# PCB_3U_BNC.net
KiCad netlist of a schematic drawn in Altium Designer
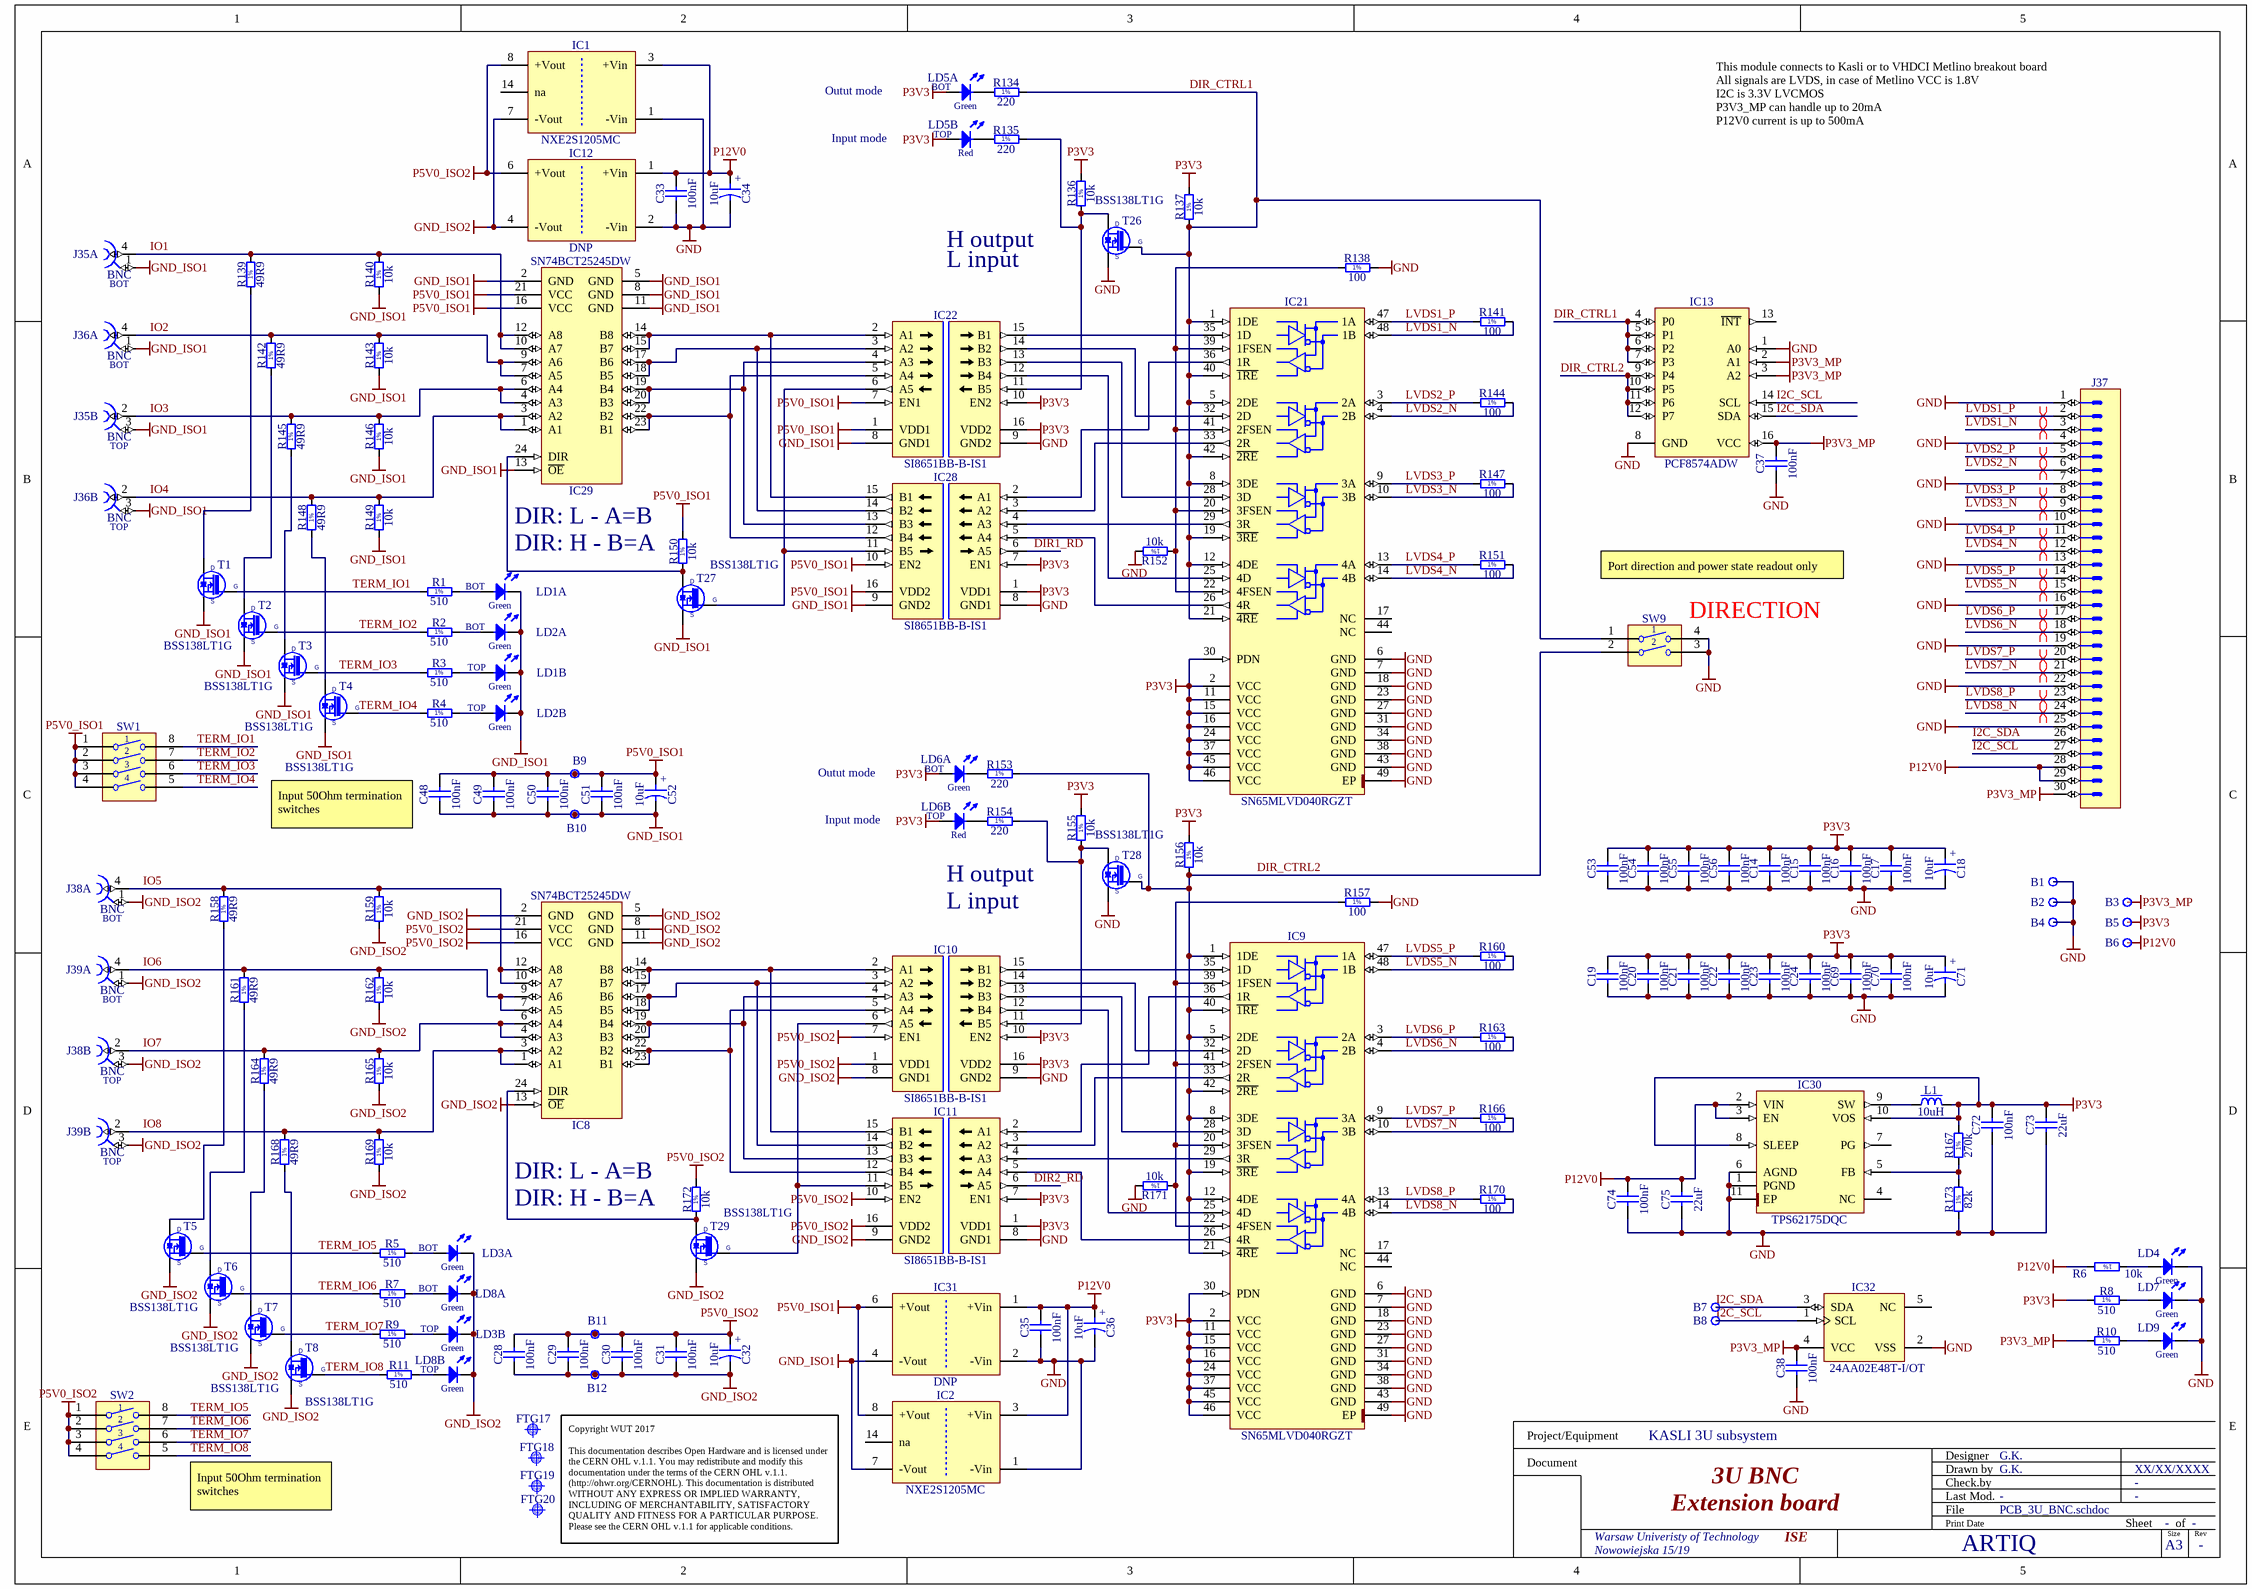
[diagram p0: PCB_3U_BNC.schdoc]

(export (version "E")
  (design (tool "Eeschema 10.0.6"))
  (components
    (comp (ref "B1")
      (value "Plated Hole")
      (footprint "c130h60")
      (description "Single Terminal Socket")
      (fields (field (name "PART NUMBER") "PLATED_HOLE0.6_PAD1.3") (field (name "AUTHOR") "CERN DEM MR"))
      (libsource (lib "Eletro-mechanical") (part "Single Terminal Socket"))
    )
    (comp (ref "B2")
      (value "Plated Hole")
      (footprint "c130h60")
      (description "Single Terminal Socket")
      (fields (field (name "PART NUMBER") "PLATED_HOLE0.6_PAD1.3") (field (name "AUTHOR") "CERN DEM MR"))
      (libsource (lib "Eletro-mechanical") (part "Single Terminal Socket"))
    )
    (comp (ref "B3")
      (value "Plated Hole")
      (footprint "c130h60")
      (description "Single Terminal Socket")
      (fields (field (name "PART NUMBER") "PLATED_HOLE0.6_PAD1.3") (field (name "AUTHOR") "CERN DEM MR"))
      (libsource (lib "Eletro-mechanical") (part "Single Terminal Socket"))
    )
    (comp (ref "B4")
      (value "Plated Hole")
      (footprint "c130h60")
      (description "Single Terminal Socket")
      (fields (field (name "PART NUMBER") "PLATED_HOLE0.6_PAD1.3") (field (name "AUTHOR") "CERN DEM MR"))
      (libsource (lib "Eletro-mechanical") (part "Single Terminal Socket"))
    )
    (comp (ref "B5")
      (value "Plated Hole")
      (footprint "c130h60")
      (description "Single Terminal Socket")
      (fields (field (name "PART NUMBER") "PLATED_HOLE0.6_PAD1.3") (field (name "AUTHOR") "CERN DEM MR"))
      (libsource (lib "Eletro-mechanical") (part "Single Terminal Socket"))
    )
    (comp (ref "B6")
      (value "Plated Hole")
      (footprint "c130h60")
      (description "Single Terminal Socket")
      (fields (field (name "PART NUMBER") "PLATED_HOLE0.6_PAD1.3") (field (name "AUTHOR") "CERN DEM MR"))
      (libsource (lib "Eletro-mechanical") (part "Single Terminal Socket"))
    )
    (comp (ref "B7")
      (value "Plated Hole")
      (footprint "c130h60")
      (description "Single Terminal Socket")
      (fields (field (name "PART NUMBER") "PLATED_HOLE0.6_PAD1.3") (field (name "AUTHOR") "CERN DEM MR"))
      (libsource (lib "Eletro-mechanical") (part "Single Terminal Socket"))
    )
    (comp (ref "B8")
      (value "Plated Hole")
      (footprint "c130h60")
      (description "Single Terminal Socket")
      (fields (field (name "PART NUMBER") "PLATED_HOLE0.6_PAD1.3") (field (name "AUTHOR") "CERN DEM MR"))
      (libsource (lib "Eletro-mechanical") (part "Single Terminal Socket"))
    )
    (comp (ref "B9")
      (value "Plated Hole")
      (footprint "c130h60")
      (description "Single Terminal Socket")
      (fields (field (name "PART NUMBER") "PLATED_HOLE0.6_PAD1.3") (field (name "AUTHOR") "CERN DEM MR"))
      (libsource (lib "Eletro-mechanical") (part "Single Terminal Socket"))
    )
    (comp (ref "B10")
      (value "Plated Hole")
      (footprint "c130h60")
      (description "Single Terminal Socket")
      (fields (field (name "PART NUMBER") "PLATED_HOLE0.6_PAD1.3") (field (name "AUTHOR") "CERN DEM MR"))
      (libsource (lib "Eletro-mechanical") (part "Single Terminal Socket"))
    )
    (comp (ref "B11")
      (value "Plated Hole")
      (footprint "c130h60")
      (description "Single Terminal Socket")
      (fields (field (name "PART NUMBER") "PLATED_HOLE0.6_PAD1.3") (field (name "AUTHOR") "CERN DEM MR"))
      (libsource (lib "Eletro-mechanical") (part "Single Terminal Socket"))
    )
    (comp (ref "B12")
      (value "Plated Hole")
      (footprint "c130h60")
      (description "Single Terminal Socket")
      (fields (field (name "PART NUMBER") "PLATED_HOLE0.6_PAD1.3") (field (name "AUTHOR") "CERN DEM MR"))
      (libsource (lib "Eletro-mechanical") (part "Single Terminal Socket"))
    )
    (comp (ref "C14")
      (value "100nF")
      (footprint "CAPC1005X55N")
      (description "Non-polarised capacitor")
      (fields
        (field (name "PART NUMBER") "CC0402_100NF_16V_10%_X5R")
        (field (name "VOLTAGE") "16V")
        (field (name "AUTHOR") "CERN DEM JLC")
      )
      (libsource (lib "Capacitors") (part "Capacitor - non polarized"))
    )
    (comp (ref "C15")
      (value "100nF")
      (footprint "CAPC1005X55N")
      (description "Non-polarised capacitor")
      (fields
        (field (name "PART NUMBER") "CC0402_100NF_16V_10%_X5R")
        (field (name "VOLTAGE") "16V")
        (field (name "AUTHOR") "CERN DEM JLC")
      )
      (libsource (lib "Capacitors") (part "Capacitor - non polarized"))
    )
    (comp (ref "C16")
      (value "100nF")
      (footprint "CAPC1005X55N")
      (description "Non-polarised capacitor")
      (fields
        (field (name "PART NUMBER") "CC0402_100NF_16V_10%_X5R")
        (field (name "VOLTAGE") "16V")
        (field (name "AUTHOR") "CERN DEM JLC")
      )
      (libsource (lib "Capacitors") (part "Capacitor - non polarized"))
    )
    (comp (ref "C17")
      (value "100nF")
      (footprint "CAPC1005X55N")
      (description "Non-polarised capacitor")
      (fields
        (field (name "PART NUMBER") "CC0402_100NF_16V_10%_X5R")
        (field (name "VOLTAGE") "16V")
        (field (name "AUTHOR") "CERN DEM JLC")
      )
      (libsource (lib "Capacitors") (part "Capacitor - non polarized"))
    )
    (comp (ref "C18")
      (value "10uF")
      (footprint "CAPAE430X540N")
      (description "Polarised capacitor")
      (fields
        (field (name "PART NUMBER") "CAE430-540_10UF_16V_20%")
        (field (name "VOLTAGE") "16V")
        (field (name "AUTHOR") "CERN DEM JLC")
      )
      (libsource (lib "Capacitors") (part "Capacitor - polarized"))
    )
    (comp (ref "C19")
      (value "100nF")
      (footprint "CAPC1005X55N")
      (description "Non-polarised capacitor")
      (fields
        (field (name "PART NUMBER") "CC0402_100NF_16V_10%_X5R")
        (field (name "VOLTAGE") "16V")
        (field (name "AUTHOR") "CERN DEM JLC")
      )
      (libsource (lib "Capacitors") (part "Capacitor - non polarized"))
    )
    (comp (ref "C20")
      (value "100nF")
      (footprint "CAPC1005X55N")
      (description "Non-polarised capacitor")
      (fields
        (field (name "PART NUMBER") "CC0402_100NF_16V_10%_X5R")
        (field (name "VOLTAGE") "16V")
        (field (name "AUTHOR") "CERN DEM JLC")
      )
      (libsource (lib "Capacitors") (part "Capacitor - non polarized"))
    )
    (comp (ref "C21")
      (value "100nF")
      (footprint "CAPC1005X55N")
      (description "Non-polarised capacitor")
      (fields
        (field (name "PART NUMBER") "CC0402_100NF_16V_10%_X5R")
        (field (name "VOLTAGE") "16V")
        (field (name "AUTHOR") "CERN DEM JLC")
      )
      (libsource (lib "Capacitors") (part "Capacitor - non polarized"))
    )
    (comp (ref "C22")
      (value "100nF")
      (footprint "CAPC1005X55N")
      (description "Non-polarised capacitor")
      (fields
        (field (name "PART NUMBER") "CC0402_100NF_16V_10%_X5R")
        (field (name "VOLTAGE") "16V")
        (field (name "AUTHOR") "CERN DEM JLC")
      )
      (libsource (lib "Capacitors") (part "Capacitor - non polarized"))
    )
    (comp (ref "C23")
      (value "100nF")
      (footprint "CAPC1005X55N")
      (description "Non-polarised capacitor")
      (fields
        (field (name "PART NUMBER") "CC0402_100NF_16V_10%_X5R")
        (field (name "VOLTAGE") "16V")
        (field (name "AUTHOR") "CERN DEM JLC")
      )
      (libsource (lib "Capacitors") (part "Capacitor - non polarized"))
    )
    (comp (ref "C24")
      (value "100nF")
      (footprint "CAPC1005X55N")
      (description "Non-polarised capacitor")
      (fields
        (field (name "PART NUMBER") "CC0402_100NF_16V_10%_X5R")
        (field (name "VOLTAGE") "16V")
        (field (name "AUTHOR") "CERN DEM JLC")
      )
      (libsource (lib "Capacitors") (part "Capacitor - non polarized"))
    )
    (comp (ref "C28")
      (value "100nF")
      (footprint "CAPC1005X55N")
      (description "Non-polarised capacitor")
      (fields
        (field (name "PART NUMBER") "CC0402_100NF_16V_10%_X5R")
        (field (name "VOLTAGE") "16V")
        (field (name "AUTHOR") "CERN DEM JLC")
      )
      (libsource (lib "Capacitors") (part "Capacitor - non polarized"))
    )
    (comp (ref "C29")
      (value "100nF")
      (footprint "CAPC1005X55N")
      (description "Non-polarised capacitor")
      (fields
        (field (name "PART NUMBER") "CC0402_100NF_16V_10%_X5R")
        (field (name "VOLTAGE") "16V")
        (field (name "AUTHOR") "CERN DEM JLC")
      )
      (libsource (lib "Capacitors") (part "Capacitor - non polarized"))
    )
    (comp (ref "C30")
      (value "100nF")
      (footprint "CAPC1005X55N")
      (description "Non-polarised capacitor")
      (fields
        (field (name "PART NUMBER") "CC0402_100NF_16V_10%_X5R")
        (field (name "VOLTAGE") "16V")
        (field (name "AUTHOR") "CERN DEM JLC")
      )
      (libsource (lib "Capacitors") (part "Capacitor - non polarized"))
    )
    (comp (ref "C31")
      (value "100nF")
      (footprint "CAPC1005X55N")
      (description "Non-polarised capacitor")
      (fields
        (field (name "PART NUMBER") "CC0402_100NF_16V_10%_X5R")
        (field (name "VOLTAGE") "16V")
        (field (name "AUTHOR") "CERN DEM JLC")
      )
      (libsource (lib "Capacitors") (part "Capacitor - non polarized"))
    )
    (comp (ref "C32")
      (value "10uF")
      (footprint "CAPAE430X540N")
      (description "Polarised capacitor")
      (fields
        (field (name "PART NUMBER") "CAE430-540_10UF_16V_20%")
        (field (name "VOLTAGE") "16V")
        (field (name "AUTHOR") "CERN DEM JLC")
      )
      (libsource (lib "Capacitors") (part "Capacitor - polarized"))
    )
    (comp (ref "C33")
      (value "100nF")
      (footprint "CAPC1005X55N")
      (description "Non-polarised capacitor")
      (fields
        (field (name "PART NUMBER") "CC0402_100NF_16V_10%_X5R")
        (field (name "VOLTAGE") "16V")
        (field (name "AUTHOR") "CERN DEM JLC")
      )
      (libsource (lib "Capacitors") (part "Capacitor - non polarized"))
    )
    (comp (ref "C34")
      (value "10uF")
      (footprint "CAPAE430X540N")
      (description "Polarised capacitor")
      (fields
        (field (name "PART NUMBER") "CAE430-540_10UF_16V_20%")
        (field (name "VOLTAGE") "16V")
        (field (name "AUTHOR") "CERN DEM JLC")
      )
      (libsource (lib "Capacitors") (part "Capacitor - polarized"))
    )
    (comp (ref "C35")
      (value "100nF")
      (footprint "CAPC1005X55N")
      (description "Non-polarised capacitor")
      (fields
        (field (name "PART NUMBER") "CC0402_100NF_16V_10%_X5R")
        (field (name "VOLTAGE") "16V")
        (field (name "AUTHOR") "CERN DEM JLC")
      )
      (libsource (lib "Capacitors") (part "Capacitor - non polarized"))
    )
    (comp (ref "C36")
      (value "10uF")
      (footprint "CAPAE430X540N")
      (description "Polarised capacitor")
      (fields
        (field (name "PART NUMBER") "CAE430-540_10UF_16V_20%")
        (field (name "VOLTAGE") "16V")
        (field (name "AUTHOR") "CERN DEM JLC")
      )
      (libsource (lib "Capacitors") (part "Capacitor - polarized"))
    )
    (comp (ref "C37")
      (value "100nF")
      (footprint "CAPC1005X55N")
      (description "Non-polarised capacitor")
      (fields
        (field (name "PART NUMBER") "CC0402_100NF_16V_10%_X5R")
        (field (name "VOLTAGE") "16V")
        (field (name "AUTHOR") "CERN DEM JLC")
      )
      (libsource (lib "Capacitors") (part "Capacitor - non polarized"))
    )
    (comp (ref "C38")
      (value "100nF")
      (footprint "CAPC1005X55N")
      (description "Non-polarised capacitor")
      (fields
        (field (name "PART NUMBER") "CC0402_100NF_16V_10%_X5R")
        (field (name "VOLTAGE") "16V")
        (field (name "AUTHOR") "CERN DEM JLC")
      )
      (libsource (lib "Capacitors") (part "Capacitor - non polarized"))
    )
    (comp (ref "C48")
      (value "100nF")
      (footprint "CAPC1005X55N")
      (description "Non-polarised capacitor")
      (fields
        (field (name "PART NUMBER") "CC0402_100NF_16V_10%_X5R")
        (field (name "VOLTAGE") "16V")
        (field (name "AUTHOR") "CERN DEM JLC")
      )
      (libsource (lib "Capacitors") (part "Capacitor - non polarized"))
    )
    (comp (ref "C49")
      (value "100nF")
      (footprint "CAPC1005X55N")
      (description "Non-polarised capacitor")
      (fields
        (field (name "PART NUMBER") "CC0402_100NF_16V_10%_X5R")
        (field (name "VOLTAGE") "16V")
        (field (name "AUTHOR") "CERN DEM JLC")
      )
      (libsource (lib "Capacitors") (part "Capacitor - non polarized"))
    )
    (comp (ref "C50")
      (value "100nF")
      (footprint "CAPC1005X55N")
      (description "Non-polarised capacitor")
      (fields
        (field (name "PART NUMBER") "CC0402_100NF_16V_10%_X5R")
        (field (name "VOLTAGE") "16V")
        (field (name "AUTHOR") "CERN DEM JLC")
      )
      (libsource (lib "Capacitors") (part "Capacitor - non polarized"))
    )
    (comp (ref "C51")
      (value "100nF")
      (footprint "CAPC1005X55N")
      (description "Non-polarised capacitor")
      (fields
        (field (name "PART NUMBER") "CC0402_100NF_16V_10%_X5R")
        (field (name "VOLTAGE") "16V")
        (field (name "AUTHOR") "CERN DEM JLC")
      )
      (libsource (lib "Capacitors") (part "Capacitor - non polarized"))
    )
    (comp (ref "C52")
      (value "10uF")
      (footprint "CAPAE430X540N")
      (description "Polarised capacitor")
      (fields
        (field (name "PART NUMBER") "CAE430-540_10UF_16V_20%")
        (field (name "VOLTAGE") "16V")
        (field (name "AUTHOR") "CERN DEM JLC")
      )
      (libsource (lib "Capacitors") (part "Capacitor - polarized"))
    )
    (comp (ref "C53")
      (value "100nF")
      (footprint "CAPC1005X55N")
      (description "Non-polarised capacitor")
      (fields
        (field (name "PART NUMBER") "CC0402_100NF_16V_10%_X5R")
        (field (name "VOLTAGE") "16V")
        (field (name "AUTHOR") "CERN DEM JLC")
      )
      (libsource (lib "Capacitors") (part "Capacitor - non polarized"))
    )
    (comp (ref "C54")
      (value "100nF")
      (footprint "CAPC1005X55N")
      (description "Non-polarised capacitor")
      (fields
        (field (name "PART NUMBER") "CC0402_100NF_16V_10%_X5R")
        (field (name "VOLTAGE") "16V")
        (field (name "AUTHOR") "CERN DEM JLC")
      )
      (libsource (lib "Capacitors") (part "Capacitor - non polarized"))
    )
    (comp (ref "C55")
      (value "100nF")
      (footprint "CAPC1005X55N")
      (description "Non-polarised capacitor")
      (fields
        (field (name "PART NUMBER") "CC0402_100NF_16V_10%_X5R")
        (field (name "VOLTAGE") "16V")
        (field (name "AUTHOR") "CERN DEM JLC")
      )
      (libsource (lib "Capacitors") (part "Capacitor - non polarized"))
    )
    (comp (ref "C56")
      (value "100nF")
      (footprint "CAPC1005X55N")
      (description "Non-polarised capacitor")
      (fields
        (field (name "PART NUMBER") "CC0402_100NF_16V_10%_X5R")
        (field (name "VOLTAGE") "16V")
        (field (name "AUTHOR") "CERN DEM JLC")
      )
      (libsource (lib "Capacitors") (part "Capacitor - non polarized"))
    )
    (comp (ref "C69")
      (value "100nF")
      (footprint "CAPC1005X55N")
      (description "Non-polarised capacitor")
      (fields
        (field (name "PART NUMBER") "CC0402_100NF_16V_10%_X5R")
        (field (name "VOLTAGE") "16V")
        (field (name "AUTHOR") "CERN DEM JLC")
      )
      (libsource (lib "Capacitors") (part "Capacitor - non polarized"))
    )
    (comp (ref "C70")
      (value "100nF")
      (footprint "CAPC1005X55N")
      (description "Non-polarised capacitor")
      (fields
        (field (name "PART NUMBER") "CC0402_100NF_16V_10%_X5R")
        (field (name "VOLTAGE") "16V")
        (field (name "AUTHOR") "CERN DEM JLC")
      )
      (libsource (lib "Capacitors") (part "Capacitor - non polarized"))
    )
    (comp (ref "C71")
      (value "10uF")
      (footprint "CAPAE430X540N")
      (description "Polarised capacitor")
      (fields
        (field (name "PART NUMBER") "CAE430-540_10UF_16V_20%")
        (field (name "VOLTAGE") "16V")
        (field (name "AUTHOR") "CERN DEM JLC")
      )
      (libsource (lib "Capacitors") (part "Capacitor - polarized"))
    )
    (comp (ref "C72")
      (value "100nF")
      (footprint "CAPC1005X55N")
      (description "Non-polarised capacitor")
      (fields
        (field (name "PART NUMBER") "CC0402_100NF_16V_10%_X5R")
        (field (name "VOLTAGE") "16V")
        (field (name "AUTHOR") "CERN DEM JLC")
      )
      (libsource (lib "Capacitors") (part "Capacitor - non polarized"))
    )
    (comp (ref "C73")
      (value "22uF")
      (footprint "CAPC2012X135N")
      (description "Non-polarised capacitor")
      (fields
        (field (name "PART NUMBER") "CC0805_22UF_16V_10%_X5R")
        (field (name "VOLTAGE") "16V")
        (field (name "AUTHOR") "CERN DEM JLC")
      )
      (libsource (lib "Capacitors") (part "Capacitor - non polarized"))
    )
    (comp (ref "C74")
      (value "100nF")
      (footprint "CAPC1005X55N")
      (description "Non-polarised capacitor")
      (fields
        (field (name "PART NUMBER") "CC0402_100NF_16V_10%_X5R")
        (field (name "VOLTAGE") "16V")
        (field (name "AUTHOR") "CERN DEM JLC")
      )
      (libsource (lib "Capacitors") (part "Capacitor - non polarized"))
    )
    (comp (ref "C75")
      (value "22uF")
      (footprint "CAPC2012X135N")
      (description "Non-polarised capacitor")
      (fields
        (field (name "PART NUMBER") "CC0805_22UF_16V_10%_X5R")
        (field (name "VOLTAGE") "16V")
        (field (name "AUTHOR") "CERN DEM JLC")
      )
      (libsource (lib "Capacitors") (part "Capacitor - non polarized"))
    )
    (comp (ref "FTG17")
      (value "Use only in PCB")
      (footprint "FIDUCIAL_TOP_C100-200")
      (description "Fiducial Target")
      (fields (field (name "PART NUMBER") "FIDUCIAL_TARGET_C100-200") (field (name "AUTHOR") "CERN DEM JLC"))
      (libsource (lib "Eletro-mechanical") (part "Fiducial Target"))
    )
    (comp (ref "FTG18")
      (value "Use only in PCB")
      (footprint "FIDUCIAL_TOP_S100-200")
      (description "Fiducial Target")
      (fields (field (name "PART NUMBER") "FIDUCIAL_TARGET_S100-200") (field (name "AUTHOR") "CERN DEM JLC"))
      (libsource (lib "Eletro-mechanical") (part "Fiducial Target"))
    )
    (comp (ref "FTG19")
      (value "Use only in PCB")
      (footprint "FIDUCIAL_TOP_S200-400")
      (description "Fiducial Target")
      (fields (field (name "PART NUMBER") "FIDUCIAL_TARGET_S200-400") (field (name "AUTHOR") "CERN DEM JLC"))
      (libsource (lib "Eletro-mechanical") (part "Fiducial Target"))
    )
    (comp (ref "FTG20")
      (value "Use only in PCB")
      (footprint "FIDUCIAL_TOP_S100-200")
      (description "Fiducial Target")
      (fields (field (name "PART NUMBER") "FIDUCIAL_TARGET_S100-200") (field (name "AUTHOR") "CERN DEM JLC"))
      (libsource (lib "Eletro-mechanical") (part "Fiducial Target"))
    )
    (comp (ref "IC1")
      (value "NXE2S1205MC")
      (footprint "DCDC_MURATA_NXE2")
      (description "MURATA, NXE2 Serie, Dual Output DCDC Converter")
      (fields (field (name "MANUFACTURER") "MURATA POWER SOLUTIONS") (field (name "AUTHOR") "CERN DEM MR"))
      (libsource (lib "LIBRARY_SCH") (part "DCDC_MURATA_NXE2S1205MC"))
    )
    (comp (ref "IC2")
      (value "NXE2S1205MC")
      (footprint "DCDC_MURATA_NXE2")
      (description "MURATA, NXE2 Serie, Dual Output DCDC Converter")
      (fields (field (name "MANUFACTURER") "MURATA POWER SOLUTIONS") (field (name "AUTHOR") "CERN DEM MR"))
      (libsource (lib "LIBRARY_SCH") (part "DCDC_MURATA_NXE2S1205MC"))
    )
    (comp (ref "IC8")
      (value "SN74BCT25245DW")
      (footprint "SOIC127P1030X265-24N")
      (description "25 Ohms Octal Bus Transceiver With 3-State Outputs")
      (fields (field (name "MANUFACTURER") "TEXAS INSTRUMENTS") (field (name "AUTHOR") "CERN DEM JLC"))
      (libsource (lib "ICs And Semiconductors") (part "7425245"))
    )
    (comp (ref "IC9")
      (value "SN65MLVD040RGZT")
      (footprint "QFN50P700X700X100-49N-S420")
      (description "4-Channel Half-Duplex M-LVDS Line Transceiver")
      (fields (field (name "MANUFACTURER") "TEXAS INSTRUMENTS") (field (name "AUTHOR") "CERN DEM JLC"))
      (libsource (lib "ICs And Semiconductors") (part "SN65MLVD040"))
    )
    (comp (ref "IC10")
      (value "SI8651BB-B-IS1")
      (footprint "SOIC127P600X175-16N")
      (description "Low Power Five-Channel Digital Isolator")
      (fields (field (name "MANUFACTURER") "SILICON LABS") (field (name "AUTHOR") "CERN DEM JLC"))
      (libsource (lib "ICs And Semiconductors") (part "Si8651"))
    )
    (comp (ref "IC11")
      (value "SI8651BB-B-IS1")
      (footprint "SOIC127P600X175-16N")
      (description "Low Power Five-Channel Digital Isolator")
      (fields (field (name "MANUFACTURER") "SILICON LABS") (field (name "AUTHOR") "CERN DEM JLC"))
      (libsource (lib "") (part "Si8651_1"))
    )
    (comp (ref "IC12")
      (value "DNP")
      (footprint "DCDC_TRACO_TMA")
      (description "1 W Watt, 10.8-13.2VDCVin, 5 V@0.2 A")
      (fields
        (field (name "PART NUMBER") "TMA 1205S")
        (field (name "MANUFACTURER") "TRACO POWER")
        (field (name "AUTHOR") "GK")
      )
      (libsource (lib "LIBRARY_SCH") (part "DC/DC_TRACO_TMA1205S"))
    )
    (comp (ref "IC13")
      (value "PCF8574ADW")
      (footprint "SOIC127P1030X265-16N")
      (description "Remote 8-bit I/O Expander For I2C Bus")
      (fields (field (name "MANUFACTURER") "TEXAS INSTRUMENTS") (field (name "AUTHOR") "CERN DEM JLC"))
      (libsource (lib "ICs And Semiconductors") (part "PCF8574ADW"))
    )
    (comp (ref "IC21")
      (value "SN65MLVD040RGZT")
      (footprint "QFN50P700X700X100-49N-S420")
      (description "4-Channel Half-Duplex M-LVDS Line Transceiver")
      (fields (field (name "MANUFACTURER") "TEXAS INSTRUMENTS") (field (name "AUTHOR") "CERN DEM JLC"))
      (libsource (lib "ICs And Semiconductors") (part "SN65MLVD040"))
    )
    (comp (ref "IC22")
      (value "SI8651BB-B-IS1")
      (footprint "SOIC127P600X175-16N")
      (description "Low Power Five-Channel Digital Isolator")
      (fields (field (name "MANUFACTURER") "SILICON LABS") (field (name "AUTHOR") "CERN DEM JLC"))
      (libsource (lib "ICs And Semiconductors") (part "Si8651"))
    )
    (comp (ref "IC28")
      (value "SI8651BB-B-IS1")
      (footprint "SOIC127P600X175-16N")
      (description "Low Power Five-Channel Digital Isolator")
      (fields (field (name "MANUFACTURER") "SILICON LABS") (field (name "AUTHOR") "CERN DEM JLC"))
      (libsource (lib "") (part "Si8651_1"))
    )
    (comp (ref "IC29")
      (value "SN74BCT25245DW")
      (footprint "SOIC127P1030X265-24N")
      (description "25 Ohms Octal Bus Transceiver With 3-State Outputs")
      (fields (field (name "MANUFACTURER") "TEXAS INSTRUMENTS") (field (name "AUTHOR") "CERN DEM JLC"))
      (libsource (lib "ICs And Semiconductors") (part "7425245"))
    )
    (comp (ref "IC30")
      (value "TPS62175DQC")
      (footprint "SON50P200X300X80-11N-R94X250")
      (description "4.75-28VDC to 1-6VDC, 500mA Step-Down Converter With Sleep Mode")
      (fields (field (name "MANUFACTURER") "TEXAS INSTRUMENTS") (field (name "AUTHOR") "CERN DEM JMW"))
      (libsource (lib "ICs And Semiconductors") (part "TPS62175"))
    )
    (comp (ref "IC31")
      (value "DNP")
      (footprint "DCDC_TRACO_TMA")
      (description "1 W Watt, 10.8-13.2VDCVin, 5 V@0.2 A")
      (fields
        (field (name "PART NUMBER") "TMA 1205S")
        (field (name "MANUFACTURER") "TRACO POWER")
        (field (name "AUTHOR") "GK")
      )
      (libsource (lib "LIBRARY_SCH") (part "DC/DC_TRACO_TMA1205S"))
    )
    (comp (ref "IC32")
      (value "24AA02E48T-I/OT")
      (footprint "SOT95P280X145-5N")
      (description "1.7V-5.5V, 2K I2C Serial EEPROM With EUI-48 Node Identity")
      (fields (field (name "MANUFACTURER") "MICROCHIP TECHNOLOGY") (field (name "AUTHOR") "CERN DEM MR"))
      (libsource (lib "ICs And Semiconductors") (part "24AA02E48T-I/OT"))
    )
    (comp (ref "J35")
      (value "BNC")
      (footprint "BOMAR_364A2595")
      (description "Dual Right Angle 50 Ohm BNC Jack, White Valox Case")
      (fields
        (field (name "PART NUMBER") "BOMAR_364A2595")
        (field (name "MANUFACTURER") "BOMAR INTERCONNECT")
        (field (name "AUTHOR") "CERN DEM JLC")
      )
      (libsource (lib "Connectors") (part "BOMAR_364A2595"))
    )
    (comp (ref "J36")
      (value "BNC")
      (footprint "BOMAR_364A2595")
      (description "Dual Right Angle 50 Ohm BNC Jack, White Valox Case")
      (fields
        (field (name "PART NUMBER") "BOMAR_364A2595")
        (field (name "MANUFACTURER") "BOMAR INTERCONNECT")
        (field (name "AUTHOR") "CERN DEM JLC")
      )
      (libsource (lib "Connectors") (part "BOMAR_364A2595"))
    )
    (comp (ref "J37")
      (value "~")
      (footprint "3M_N2530-6002RB")
      (description "Connector 30 Male")
      (fields
        (field (name "PART NUMBER") "3M_N2530-6002RB")
        (field (name "MANUFACTURER") "3M")
        (field (name "AUTHOR") "CERN DEM JLC")
      )
      (libsource (lib "Connectors") (part "Connector 30 Male"))
    )
    (comp (ref "J38")
      (value "BNC")
      (footprint "BOMAR_364A2595")
      (description "Dual Right Angle 50 Ohm BNC Jack, White Valox Case")
      (fields
        (field (name "PART NUMBER") "BOMAR_364A2595")
        (field (name "MANUFACTURER") "BOMAR INTERCONNECT")
        (field (name "AUTHOR") "CERN DEM JLC")
      )
      (libsource (lib "Connectors") (part "BOMAR_364A2595"))
    )
    (comp (ref "J39")
      (value "BNC")
      (footprint "BOMAR_364A2595")
      (description "Dual Right Angle 50 Ohm BNC Jack, White Valox Case")
      (fields
        (field (name "PART NUMBER") "BOMAR_364A2595")
        (field (name "MANUFACTURER") "BOMAR INTERCONNECT")
        (field (name "AUTHOR") "CERN DEM JLC")
      )
      (libsource (lib "Connectors") (part "BOMAR_364A2595"))
    )
    (comp (ref "L1")
      (value "10uH")
      (footprint "IND_MURATA-PS_8400")
      (description "Inductor With Core")
      (fields
        (field (name "PART NUMBER") "IND_10UH_10%_MURATA-PS_8400")
        (field (name "POWER") "950mA")
        (field (name "AUTHOR") "CERN DEM JLC")
      )
      (libsource (lib "Inductors & Transformers") (part "Inductor With Magnetic core"))
    )
    (comp (ref "LD1")
      (value "Green/Green")
      (footprint "LED_DIALIGHT_571-0122F")
      (description "LED x2 Green 1C2A-BOT_3C4A-TOP")
      (fields
        (field (name "PART NUMBER") "LED_DIALIGHT_571-0122F")
        (field (name "MANUFACTURER") "DIALIGHT")
        (field (name "AUTHOR") "CERN DEM JLC")
      )
      (libsource (lib "ICs And Semiconductors") (part "LED x2 Green 1C2A-BOT_3C4A-TOP"))
    )
    (comp (ref "LD2")
      (value "Green/Green")
      (footprint "LED_DIALIGHT_571-0122F")
      (description "LED x2 Green 1C2A-BOT_3C4A-TOP")
      (fields
        (field (name "PART NUMBER") "LED_DIALIGHT_571-0122F")
        (field (name "MANUFACTURER") "DIALIGHT")
        (field (name "AUTHOR") "CERN DEM JLC")
      )
      (libsource (lib "ICs And Semiconductors") (part "LED x2 Green 1C2A-BOT_3C4A-TOP"))
    )
    (comp (ref "LD3")
      (value "Green/Green")
      (footprint "LED_DIALIGHT_571-0122F")
      (description "LED x2 Green 1C2A-BOT_3C4A-TOP")
      (fields
        (field (name "PART NUMBER") "LED_DIALIGHT_571-0122F")
        (field (name "MANUFACTURER") "DIALIGHT")
        (field (name "AUTHOR") "CERN DEM JLC")
      )
      (libsource (lib "ICs And Semiconductors") (part "LED x2 Green 1C2A-BOT_3C4A-TOP"))
    )
    (comp (ref "LD4")
      (value "Green")
      (footprint "LED_KINGBRIGHT_KPH-1608CGCK")
      (description "LED Green 1C 2A")
      (fields
        (field (name "PART NUMBER") "LED_KINGBRIGHT_KPH-1608CGCK")
        (field (name "MANUFACTURER") "KINGBRIGHT")
        (field (name "AUTHOR") "CERN DEM JLC")
      )
      (libsource (lib "ICs And Semiconductors") (part "LED Green 1C 2A"))
    )
    (comp (ref "LD5")
      (value "Red/Green")
      (footprint "LED_DIALIGHT_571-0112F")
      (description "2x LED  Botom Green, Top Red")
      (fields
        (field (name "PART NUMBER") "LED_DIALIGHT_571-0112F")
        (field (name "MANUFACTURER") "DIALIGHT")
        (field (name "AUTHOR") "CERN DEM JLC")
      )
      (libsource (lib "ICs And Semiconductors") (part "LED x2 G-1C2A-BOT_R-3C4A-TOP"))
    )
    (comp (ref "LD6")
      (value "Red/Green")
      (footprint "LED_DIALIGHT_571-0112F")
      (description "2x LED  Botom Green, Top Red")
      (fields
        (field (name "PART NUMBER") "LED_DIALIGHT_571-0112F")
        (field (name "MANUFACTURER") "DIALIGHT")
        (field (name "AUTHOR") "CERN DEM JLC")
      )
      (libsource (lib "ICs And Semiconductors") (part "LED x2 G-1C2A-BOT_R-3C4A-TOP"))
    )
    (comp (ref "LD7")
      (value "Green")
      (footprint "LED_KINGBRIGHT_KPH-1608CGCK")
      (description "LED Green 1C 2A")
      (fields
        (field (name "PART NUMBER") "LED_KINGBRIGHT_KPH-1608CGCK")
        (field (name "MANUFACTURER") "KINGBRIGHT")
        (field (name "AUTHOR") "CERN DEM JLC")
      )
      (libsource (lib "ICs And Semiconductors") (part "LED Green 1C 2A"))
    )
    (comp (ref "LD8")
      (value "Green/Green")
      (footprint "LED_DIALIGHT_571-0122F")
      (description "LED x2 Green 1C2A-BOT_3C4A-TOP")
      (fields
        (field (name "PART NUMBER") "LED_DIALIGHT_571-0122F")
        (field (name "MANUFACTURER") "DIALIGHT")
        (field (name "AUTHOR") "CERN DEM JLC")
      )
      (libsource (lib "ICs And Semiconductors") (part "LED x2 Green 1C2A-BOT_3C4A-TOP"))
    )
    (comp (ref "LD9")
      (value "Green")
      (footprint "LED_KINGBRIGHT_KPH-1608CGCK")
      (description "LED Green 1C 2A")
      (fields
        (field (name "PART NUMBER") "LED_KINGBRIGHT_KPH-1608CGCK")
        (field (name "MANUFACTURER") "KINGBRIGHT")
        (field (name "AUTHOR") "CERN DEM JLC")
      )
      (libsource (lib "ICs And Semiconductors") (part "LED Green 1C 2A"))
    )
    (comp (ref "R1")
      (value "510")
      (footprint "RESC1005X40N")
      (description "Resistor - 1%")
      (fields
        (field (name "PART NUMBER") "R0402_510R_1%_0.0625W_100PPM")
        (field (name "POWER") "0.0625W")
        (field (name "AUTHOR") "CERN DEM JLC")
      )
      (libsource (lib "Resistors") (part "Resistor - 1%"))
    )
    (comp (ref "R2")
      (value "510")
      (footprint "RESC1005X40N")
      (description "Resistor - 1%")
      (fields
        (field (name "PART NUMBER") "R0402_510R_1%_0.0625W_100PPM")
        (field (name "POWER") "0.0625W")
        (field (name "AUTHOR") "CERN DEM JLC")
      )
      (libsource (lib "Resistors") (part "Resistor - 1%"))
    )
    (comp (ref "R3")
      (value "510")
      (footprint "RESC1005X40N")
      (description "Resistor - 1%")
      (fields
        (field (name "PART NUMBER") "R0402_510R_1%_0.0625W_100PPM")
        (field (name "POWER") "0.0625W")
        (field (name "AUTHOR") "CERN DEM JLC")
      )
      (libsource (lib "Resistors") (part "Resistor - 1%"))
    )
    (comp (ref "R4")
      (value "510")
      (footprint "RESC1005X40N")
      (description "Resistor - 1%")
      (fields
        (field (name "PART NUMBER") "R0402_510R_1%_0.0625W_100PPM")
        (field (name "POWER") "0.0625W")
        (field (name "AUTHOR") "CERN DEM JLC")
      )
      (libsource (lib "Resistors") (part "Resistor - 1%"))
    )
    (comp (ref "R5")
      (value "510")
      (footprint "RESC1005X40N")
      (description "Resistor - 1%")
      (fields
        (field (name "PART NUMBER") "R0402_510R_1%_0.0625W_100PPM")
        (field (name "POWER") "0.0625W")
        (field (name "AUTHOR") "CERN DEM JLC")
      )
      (libsource (lib "Resistors") (part "Resistor - 1%"))
    )
    (comp (ref "R6")
      (value "10k")
      (footprint "RESC1005X40N")
      (description "Resistor - 1%")
      (fields
        (field (name "PART NUMBER") "R0402_10K_1%_0.0625W_100PPM")
        (field (name "POWER") "0.0625W")
        (field (name "AUTHOR") "CERN DEM JLC")
      )
      (libsource (lib "Resistors") (part "Resistor - 1%"))
    )
    (comp (ref "R7")
      (value "510")
      (footprint "RESC1005X40N")
      (description "Resistor - 1%")
      (fields
        (field (name "PART NUMBER") "R0402_510R_1%_0.0625W_100PPM")
        (field (name "POWER") "0.0625W")
        (field (name "AUTHOR") "CERN DEM JLC")
      )
      (libsource (lib "Resistors") (part "Resistor - 1%"))
    )
    (comp (ref "R8")
      (value "510")
      (footprint "RESC1005X40N")
      (description "Resistor - 1%")
      (fields
        (field (name "PART NUMBER") "R0402_510R_1%_0.0625W_100PPM")
        (field (name "POWER") "0.0625W")
        (field (name "AUTHOR") "CERN DEM JLC")
      )
      (libsource (lib "Resistors") (part "Resistor - 1%"))
    )
    (comp (ref "R9")
      (value "510")
      (footprint "RESC1005X40N")
      (description "Resistor - 1%")
      (fields
        (field (name "PART NUMBER") "R0402_510R_1%_0.0625W_100PPM")
        (field (name "POWER") "0.0625W")
        (field (name "AUTHOR") "CERN DEM JLC")
      )
      (libsource (lib "Resistors") (part "Resistor - 1%"))
    )
    (comp (ref "R10")
      (value "510")
      (footprint "RESC1005X40N")
      (description "Resistor - 1%")
      (fields
        (field (name "PART NUMBER") "R0402_510R_1%_0.0625W_100PPM")
        (field (name "POWER") "0.0625W")
        (field (name "AUTHOR") "CERN DEM JLC")
      )
      (libsource (lib "Resistors") (part "Resistor - 1%"))
    )
    (comp (ref "R11")
      (value "510")
      (footprint "RESC1005X40N")
      (description "Resistor - 1%")
      (fields
        (field (name "PART NUMBER") "R0402_510R_1%_0.0625W_100PPM")
        (field (name "POWER") "0.0625W")
        (field (name "AUTHOR") "CERN DEM JLC")
      )
      (libsource (lib "Resistors") (part "Resistor - 1%"))
    )
    (comp (ref "R134")
      (value "220")
      (footprint "RESC1608X55N")
      (description "Resistor - 1%")
      (fields
        (field (name "PART NUMBER") "R0603_220R_1%_0.1W_100PPM")
        (field (name "POWER") "0.1W")
        (field (name "AUTHOR") "CERN DEM JLC")
      )
      (libsource (lib "Resistors") (part "Resistor - 1%"))
    )
    (comp (ref "R135")
      (value "220")
      (footprint "RESC1608X55N")
      (description "Resistor - 1%")
      (fields
        (field (name "PART NUMBER") "R0603_220R_1%_0.1W_100PPM")
        (field (name "POWER") "0.1W")
        (field (name "AUTHOR") "CERN DEM JLC")
      )
      (libsource (lib "Resistors") (part "Resistor - 1%"))
    )
    (comp (ref "R136")
      (value "10k")
      (footprint "RESC1005X40N")
      (description "Resistor - 1%")
      (fields
        (field (name "PART NUMBER") "R0402_10K_1%_0.0625W_100PPM")
        (field (name "POWER") "0.0625W")
        (field (name "AUTHOR") "CERN DEM JLC")
      )
      (libsource (lib "Resistors") (part "Resistor - 1%"))
    )
    (comp (ref "R137")
      (value "10k")
      (footprint "RESC1005X40N")
      (description "Resistor - 1%")
      (fields
        (field (name "PART NUMBER") "R0402_10K_1%_0.0625W_100PPM")
        (field (name "POWER") "0.0625W")
        (field (name "AUTHOR") "CERN DEM JLC")
      )
      (libsource (lib "Resistors") (part "Resistor - 1%"))
    )
    (comp (ref "R138")
      (value "100")
      (footprint "RESC1005X40N")
      (description "Resistor - 1%")
      (fields
        (field (name "PART NUMBER") "R0402_100R_1%_0.1W_100PPM")
        (field (name "POWER") "0.1W")
        (field (name "AUTHOR") "CERN DEM JLC")
      )
      (libsource (lib "Resistors") (part "Resistor - 1%"))
    )
    (comp (ref "R139")
      (value "49R9")
      (footprint "RESC3225X70N")
      (description "Resistor - 1%")
      (fields
        (field (name "PART NUMBER") "R1210_49R9_1%_0.5W_100PPM_VISHAY_CRCW")
        (field (name "POWER") "0.5W")
        (field (name "AUTHOR") "CERN DEM JMW")
      )
      (libsource (lib "Resistors") (part "Resistor - 1%"))
    )
    (comp (ref "R140")
      (value "10k")
      (footprint "RESC1005X40N")
      (description "Resistor - 1%")
      (fields
        (field (name "PART NUMBER") "R0402_10K_1%_0.0625W_100PPM")
        (field (name "POWER") "0.0625W")
        (field (name "AUTHOR") "CERN DEM JLC")
      )
      (libsource (lib "Resistors") (part "Resistor - 1%"))
    )
    (comp (ref "R141")
      (value "100")
      (footprint "RESC1005X40N")
      (description "Resistor - 1%")
      (fields
        (field (name "PART NUMBER") "R0402_100R_1%_0.1W_100PPM")
        (field (name "POWER") "0.1W")
        (field (name "AUTHOR") "CERN DEM JLC")
      )
      (libsource (lib "Resistors") (part "Resistor - 1%"))
    )
    (comp (ref "R142")
      (value "49R9")
      (footprint "RESC3225X70N")
      (description "Resistor - 1%")
      (fields
        (field (name "PART NUMBER") "R1210_49R9_1%_0.5W_100PPM_VISHAY_CRCW")
        (field (name "POWER") "0.5W")
        (field (name "AUTHOR") "CERN DEM JMW")
      )
      (libsource (lib "Resistors") (part "Resistor - 1%"))
    )
    (comp (ref "R143")
      (value "10k")
      (footprint "RESC1005X40N")
      (description "Resistor - 1%")
      (fields
        (field (name "PART NUMBER") "R0402_10K_1%_0.0625W_100PPM")
        (field (name "POWER") "0.0625W")
        (field (name "AUTHOR") "CERN DEM JLC")
      )
      (libsource (lib "Resistors") (part "Resistor - 1%"))
    )
    (comp (ref "R144")
      (value "100")
      (footprint "RESC1005X40N")
      (description "Resistor - 1%")
      (fields
        (field (name "PART NUMBER") "R0402_100R_1%_0.1W_100PPM")
        (field (name "POWER") "0.1W")
        (field (name "AUTHOR") "CERN DEM JLC")
      )
      (libsource (lib "Resistors") (part "Resistor - 1%"))
    )
    (comp (ref "R145")
      (value "49R9")
      (footprint "RESC3225X70N")
      (description "Resistor - 1%")
      (fields
        (field (name "PART NUMBER") "R1210_49R9_1%_0.5W_100PPM_VISHAY_CRCW")
        (field (name "POWER") "0.5W")
        (field (name "AUTHOR") "CERN DEM JMW")
      )
      (libsource (lib "Resistors") (part "Resistor - 1%"))
    )
    (comp (ref "R146")
      (value "10k")
      (footprint "RESC1005X40N")
      (description "Resistor - 1%")
      (fields
        (field (name "PART NUMBER") "R0402_10K_1%_0.0625W_100PPM")
        (field (name "POWER") "0.0625W")
        (field (name "AUTHOR") "CERN DEM JLC")
      )
      (libsource (lib "Resistors") (part "Resistor - 1%"))
    )
    (comp (ref "R147")
      (value "100")
      (footprint "RESC1005X40N")
      (description "Resistor - 1%")
      (fields
        (field (name "PART NUMBER") "R0402_100R_1%_0.1W_100PPM")
        (field (name "POWER") "0.1W")
        (field (name "AUTHOR") "CERN DEM JLC")
      )
      (libsource (lib "Resistors") (part "Resistor - 1%"))
    )
    (comp (ref "R148")
      (value "49R9")
      (footprint "RESC3225X70N")
      (description "Resistor - 1%")
      (fields
        (field (name "PART NUMBER") "R1210_49R9_1%_0.5W_100PPM_VISHAY_CRCW")
        (field (name "POWER") "0.5W")
        (field (name "AUTHOR") "CERN DEM JMW")
      )
      (libsource (lib "Resistors") (part "Resistor - 1%"))
    )
    (comp (ref "R149")
      (value "10k")
      (footprint "RESC1005X40N")
      (description "Resistor - 1%")
      (fields
        (field (name "PART NUMBER") "R0402_10K_1%_0.0625W_100PPM")
        (field (name "POWER") "0.0625W")
        (field (name "AUTHOR") "CERN DEM JLC")
      )
      (libsource (lib "Resistors") (part "Resistor - 1%"))
    )
    (comp (ref "R150")
      (value "10k")
      (footprint "RESC1005X40N")
      (description "Resistor - 1%")
      (fields
        (field (name "PART NUMBER") "R0402_10K_1%_0.0625W_100PPM")
        (field (name "POWER") "0.0625W")
        (field (name "AUTHOR") "CERN DEM JLC")
      )
      (libsource (lib "Resistors") (part "Resistor - 1%"))
    )
    (comp (ref "R151")
      (value "100")
      (footprint "RESC1005X40N")
      (description "Resistor - 1%")
      (fields
        (field (name "PART NUMBER") "R0402_100R_1%_0.1W_100PPM")
        (field (name "POWER") "0.1W")
        (field (name "AUTHOR") "CERN DEM JLC")
      )
      (libsource (lib "Resistors") (part "Resistor - 1%"))
    )
    (comp (ref "R152")
      (value "10k")
      (footprint "RESC1005X40N")
      (description "Resistor - 1%")
      (fields
        (field (name "PART NUMBER") "R0402_10K_1%_0.0625W_100PPM")
        (field (name "POWER") "0.0625W")
        (field (name "AUTHOR") "CERN DEM JLC")
      )
      (libsource (lib "Resistors") (part "Resistor - 1%"))
    )
    (comp (ref "R153")
      (value "220")
      (footprint "RESC1608X55N")
      (description "Resistor - 1%")
      (fields
        (field (name "PART NUMBER") "R0603_220R_1%_0.1W_100PPM")
        (field (name "POWER") "0.1W")
        (field (name "AUTHOR") "CERN DEM JLC")
      )
      (libsource (lib "Resistors") (part "Resistor - 1%"))
    )
    (comp (ref "R154")
      (value "220")
      (footprint "RESC1608X55N")
      (description "Resistor - 1%")
      (fields
        (field (name "PART NUMBER") "R0603_220R_1%_0.1W_100PPM")
        (field (name "POWER") "0.1W")
        (field (name "AUTHOR") "CERN DEM JLC")
      )
      (libsource (lib "Resistors") (part "Resistor - 1%"))
    )
    (comp (ref "R155")
      (value "10k")
      (footprint "RESC1005X40N")
      (description "Resistor - 1%")
      (fields
        (field (name "PART NUMBER") "R0402_10K_1%_0.0625W_100PPM")
        (field (name "POWER") "0.0625W")
        (field (name "AUTHOR") "CERN DEM JLC")
      )
      (libsource (lib "Resistors") (part "Resistor - 1%"))
    )
    (comp (ref "R156")
      (value "10k")
      (footprint "RESC1005X40N")
      (description "Resistor - 1%")
      (fields
        (field (name "PART NUMBER") "R0402_10K_1%_0.0625W_100PPM")
        (field (name "POWER") "0.0625W")
        (field (name "AUTHOR") "CERN DEM JLC")
      )
      (libsource (lib "Resistors") (part "Resistor - 1%"))
    )
    (comp (ref "R157")
      (value "100")
      (footprint "RESC1005X40N")
      (description "Resistor - 1%")
      (fields
        (field (name "PART NUMBER") "R0402_100R_1%_0.1W_100PPM")
        (field (name "POWER") "0.1W")
        (field (name "AUTHOR") "CERN DEM JLC")
      )
      (libsource (lib "Resistors") (part "Resistor - 1%"))
    )
    (comp (ref "R158")
      (value "49R9")
      (footprint "RESC3225X70N")
      (description "Resistor - 1%")
      (fields
        (field (name "PART NUMBER") "R1210_49R9_1%_0.5W_100PPM_VISHAY_CRCW")
        (field (name "POWER") "0.5W")
        (field (name "AUTHOR") "CERN DEM JMW")
      )
      (libsource (lib "Resistors") (part "Resistor - 1%"))
    )
    (comp (ref "R159")
      (value "10k")
      (footprint "RESC1005X40N")
      (description "Resistor - 1%")
      (fields
        (field (name "PART NUMBER") "R0402_10K_1%_0.0625W_100PPM")
        (field (name "POWER") "0.0625W")
        (field (name "AUTHOR") "CERN DEM JLC")
      )
      (libsource (lib "Resistors") (part "Resistor - 1%"))
    )
    (comp (ref "R160")
      (value "100")
      (footprint "RESC1005X40N")
      (description "Resistor - 1%")
      (fields
        (field (name "PART NUMBER") "R0402_100R_1%_0.1W_100PPM")
        (field (name "POWER") "0.1W")
        (field (name "AUTHOR") "CERN DEM JLC")
      )
      (libsource (lib "Resistors") (part "Resistor - 1%"))
    )
    (comp (ref "R161")
      (value "49R9")
      (footprint "RESC3225X70N")
      (description "Resistor - 1%")
      (fields
        (field (name "PART NUMBER") "R1210_49R9_1%_0.5W_100PPM_VISHAY_CRCW")
        (field (name "POWER") "0.5W")
        (field (name "AUTHOR") "CERN DEM JMW")
      )
      (libsource (lib "Resistors") (part "Resistor - 1%"))
    )
    (comp (ref "R162")
      (value "10k")
      (footprint "RESC1005X40N")
      (description "Resistor - 1%")
      (fields
        (field (name "PART NUMBER") "R0402_10K_1%_0.0625W_100PPM")
        (field (name "POWER") "0.0625W")
        (field (name "AUTHOR") "CERN DEM JLC")
      )
      (libsource (lib "Resistors") (part "Resistor - 1%"))
    )
    (comp (ref "R163")
      (value "100")
      (footprint "RESC1005X40N")
      (description "Resistor - 1%")
      (fields
        (field (name "PART NUMBER") "R0402_100R_1%_0.1W_100PPM")
        (field (name "POWER") "0.1W")
        (field (name "AUTHOR") "CERN DEM JLC")
      )
      (libsource (lib "Resistors") (part "Resistor - 1%"))
    )
    (comp (ref "R164")
      (value "49R9")
      (footprint "RESC3225X70N")
      (description "Resistor - 1%")
      (fields
        (field (name "PART NUMBER") "R1210_49R9_1%_0.5W_100PPM_VISHAY_CRCW")
        (field (name "POWER") "0.5W")
        (field (name "AUTHOR") "CERN DEM JMW")
      )
      (libsource (lib "Resistors") (part "Resistor - 1%"))
    )
    (comp (ref "R165")
      (value "10k")
      (footprint "RESC1005X40N")
      (description "Resistor - 1%")
      (fields
        (field (name "PART NUMBER") "R0402_10K_1%_0.0625W_100PPM")
        (field (name "POWER") "0.0625W")
        (field (name "AUTHOR") "CERN DEM JLC")
      )
      (libsource (lib "Resistors") (part "Resistor - 1%"))
    )
    (comp (ref "R166")
      (value "100")
      (footprint "RESC1005X40N")
      (description "Resistor - 1%")
      (fields
        (field (name "PART NUMBER") "R0402_100R_1%_0.1W_100PPM")
        (field (name "POWER") "0.1W")
        (field (name "AUTHOR") "CERN DEM JLC")
      )
      (libsource (lib "Resistors") (part "Resistor - 1%"))
    )
    (comp (ref "R167")
      (value "270k")
      (footprint "RESC1608X55N")
      (description "Resistor - 1%")
      (fields
        (field (name "PART NUMBER") "R0603_270K_1%_0.1W_100PPM")
        (field (name "POWER") "0.1W")
        (field (name "AUTHOR") "CERN DEM JLC")
      )
      (libsource (lib "Resistors") (part "Resistor - 1%"))
    )
    (comp (ref "R168")
      (value "49R9")
      (footprint "RESC3225X70N")
      (description "Resistor - 1%")
      (fields
        (field (name "PART NUMBER") "R1210_49R9_1%_0.5W_100PPM_VISHAY_CRCW")
        (field (name "POWER") "0.5W")
        (field (name "AUTHOR") "CERN DEM JMW")
      )
      (libsource (lib "Resistors") (part "Resistor - 1%"))
    )
    (comp (ref "R169")
      (value "10k")
      (footprint "RESC1005X40N")
      (description "Resistor - 1%")
      (fields
        (field (name "PART NUMBER") "R0402_10K_1%_0.0625W_100PPM")
        (field (name "POWER") "0.0625W")
        (field (name "AUTHOR") "CERN DEM JLC")
      )
      (libsource (lib "Resistors") (part "Resistor - 1%"))
    )
    (comp (ref "R170")
      (value "100")
      (footprint "RESC1005X40N")
      (description "Resistor - 1%")
      (fields
        (field (name "PART NUMBER") "R0402_100R_1%_0.1W_100PPM")
        (field (name "POWER") "0.1W")
        (field (name "AUTHOR") "CERN DEM JLC")
      )
      (libsource (lib "Resistors") (part "Resistor - 1%"))
    )
    (comp (ref "R171")
      (value "10k")
      (footprint "RESC1005X40N")
      (description "Resistor - 1%")
      (fields
        (field (name "PART NUMBER") "R0402_10K_1%_0.0625W_100PPM")
        (field (name "POWER") "0.0625W")
        (field (name "AUTHOR") "CERN DEM JLC")
      )
      (libsource (lib "Resistors") (part "Resistor - 1%"))
    )
    (comp (ref "R172")
      (value "10k")
      (footprint "RESC1005X40N")
      (description "Resistor - 1%")
      (fields
        (field (name "PART NUMBER") "R0402_10K_1%_0.0625W_100PPM")
        (field (name "POWER") "0.0625W")
        (field (name "AUTHOR") "CERN DEM JLC")
      )
      (libsource (lib "Resistors") (part "Resistor - 1%"))
    )
    (comp (ref "R173")
      (value "82k")
      (footprint "RESC1608X55N")
      (description "Resistor - 1%")
      (fields
        (field (name "PART NUMBER") "R0603_82K_1%_0.1W_100PPM")
        (field (name "POWER") "0.1W")
        (field (name "AUTHOR") "CERN DEM JLC")
      )
      (libsource (lib "Resistors") (part "Resistor - 1%"))
    )
    (comp (ref "SW1")
      (value "Switch")
      (footprint "SW_OMRON_A6S-4102-H")
      (description "4 Ways SPST DIP Switch")
      (fields
        (field (name "PART NUMBER") "SW_OMRON_A6S-4102-H")
        (field (name "MANUFACTURER") "OMRON")
        (field (name "AUTHOR") "CERN DEM JMW")
      )
      (libsource (lib "Eletro-mechanical") (part "SW 4x SPST DIP Switch"))
    )
    (comp (ref "SW2")
      (value "Switch")
      (footprint "SW_OMRON_A6S-4102-H")
      (description "4 Ways SPST DIP Switch")
      (fields
        (field (name "PART NUMBER") "SW_OMRON_A6S-4102-H")
        (field (name "MANUFACTURER") "OMRON")
        (field (name "AUTHOR") "CERN DEM JMW")
      )
      (libsource (lib "Eletro-mechanical") (part "SW 4x SPST DIP Switch"))
    )
    (comp (ref "SW9")
      (value "Switch")
      (footprint "SW_OMRON_A6S-2102-H")
      (description "2 Ways SPST DIP Switch")
      (fields
        (field (name "PART NUMBER") "SW_OMRON_A6S-2102-H")
        (field (name "MANUFACTURER") "OMRON")
        (field (name "AUTHOR") "CERN DEM JMW")
      )
      (libsource (lib "Eletro-mechanical") (part "SW 2x SPST DIP Switch"))
    )
    (comp (ref "T1")
      (value "BSS138LT1G")
      (footprint "SOT95P240X110-3N")
      (description "N-CHANNEL MOSFET WITH DIODE")
      (fields (field (name "MANUFACTURER") "ON SEMICONDUCTOR") (field (name "AUTHOR") "CERN DEM JLC"))
      (libsource (lib "ICs And Semiconductors") (part "N-MOSFET-D 1G 2S 3D"))
    )
    (comp (ref "T2")
      (value "BSS138LT1G")
      (footprint "SOT95P240X110-3N")
      (description "N-CHANNEL MOSFET WITH DIODE")
      (fields (field (name "MANUFACTURER") "ON SEMICONDUCTOR") (field (name "AUTHOR") "CERN DEM JLC"))
      (libsource (lib "ICs And Semiconductors") (part "N-MOSFET-D 1G 2S 3D"))
    )
    (comp (ref "T3")
      (value "BSS138LT1G")
      (footprint "SOT95P240X110-3N")
      (description "N-CHANNEL MOSFET WITH DIODE")
      (fields (field (name "MANUFACTURER") "ON SEMICONDUCTOR") (field (name "AUTHOR") "CERN DEM JLC"))
      (libsource (lib "ICs And Semiconductors") (part "N-MOSFET-D 1G 2S 3D"))
    )
    (comp (ref "T4")
      (value "BSS138LT1G")
      (footprint "SOT95P240X110-3N")
      (description "N-CHANNEL MOSFET WITH DIODE")
      (fields (field (name "MANUFACTURER") "ON SEMICONDUCTOR") (field (name "AUTHOR") "CERN DEM JLC"))
      (libsource (lib "ICs And Semiconductors") (part "N-MOSFET-D 1G 2S 3D"))
    )
    (comp (ref "T5")
      (value "BSS138LT1G")
      (footprint "SOT95P240X110-3N")
      (description "N-CHANNEL MOSFET WITH DIODE")
      (fields (field (name "MANUFACTURER") "ON SEMICONDUCTOR") (field (name "AUTHOR") "CERN DEM JLC"))
      (libsource (lib "ICs And Semiconductors") (part "N-MOSFET-D 1G 2S 3D"))
    )
    (comp (ref "T6")
      (value "BSS138LT1G")
      (footprint "SOT95P240X110-3N")
      (description "N-CHANNEL MOSFET WITH DIODE")
      (fields (field (name "MANUFACTURER") "ON SEMICONDUCTOR") (field (name "AUTHOR") "CERN DEM JLC"))
      (libsource (lib "ICs And Semiconductors") (part "N-MOSFET-D 1G 2S 3D"))
    )
    (comp (ref "T7")
      (value "BSS138LT1G")
      (footprint "SOT95P240X110-3N")
      (description "N-CHANNEL MOSFET WITH DIODE")
      (fields (field (name "MANUFACTURER") "ON SEMICONDUCTOR") (field (name "AUTHOR") "CERN DEM JLC"))
      (libsource (lib "ICs And Semiconductors") (part "N-MOSFET-D 1G 2S 3D"))
    )
    (comp (ref "T8")
      (value "BSS138LT1G")
      (footprint "SOT95P240X110-3N")
      (description "N-CHANNEL MOSFET WITH DIODE")
      (fields (field (name "MANUFACTURER") "ON SEMICONDUCTOR") (field (name "AUTHOR") "CERN DEM JLC"))
      (libsource (lib "ICs And Semiconductors") (part "N-MOSFET-D 1G 2S 3D"))
    )
    (comp (ref "T26")
      (value "BSS138LT1G")
      (footprint "SOT95P240X110-3N")
      (description "N-CHANNEL MOSFET WITH DIODE")
      (fields (field (name "MANUFACTURER") "ON SEMICONDUCTOR") (field (name "AUTHOR") "CERN DEM JLC"))
      (libsource (lib "ICs And Semiconductors") (part "N-MOSFET-D 1G 2S 3D"))
    )
    (comp (ref "T27")
      (value "BSS138LT1G")
      (footprint "SOT95P240X110-3N")
      (description "N-CHANNEL MOSFET WITH DIODE")
      (fields (field (name "MANUFACTURER") "ON SEMICONDUCTOR") (field (name "AUTHOR") "CERN DEM JLC"))
      (libsource (lib "ICs And Semiconductors") (part "N-MOSFET-D 1G 2S 3D"))
    )
    (comp (ref "T28")
      (value "BSS138LT1G")
      (footprint "SOT95P240X110-3N")
      (description "N-CHANNEL MOSFET WITH DIODE")
      (fields (field (name "MANUFACTURER") "ON SEMICONDUCTOR") (field (name "AUTHOR") "CERN DEM JLC"))
      (libsource (lib "ICs And Semiconductors") (part "N-MOSFET-D 1G 2S 3D"))
    )
    (comp (ref "T29")
      (value "BSS138LT1G")
      (footprint "SOT95P240X110-3N")
      (description "N-CHANNEL MOSFET WITH DIODE")
      (fields (field (name "MANUFACTURER") "ON SEMICONDUCTOR") (field (name "AUTHOR") "CERN DEM JLC"))
      (libsource (lib "ICs And Semiconductors") (part "N-MOSFET-D 1G 2S 3D"))
    )
  )
  (nets
    (net (code "1") (name "/DIR1_RD") (class "Default")
      (node (ref "IC28") (pin "6") (pinfunction "A5_6") (pintype "output"))
    )
    (net (code "2") (name "/DIR2_RD") (class "Default")
      (node (ref "IC11") (pin "6") (pinfunction "A5_6") (pintype "output"))
    )
    (net (code "3") (name "/DIR_CTRL1") (class "Default")
      (node (ref "IC13") (pin "4") (pinfunction "P0_4") (pintype "bidirectional"))
      (node (ref "IC13") (pin "5") (pinfunction "P1_5") (pintype "bidirectional"))
      (node (ref "IC13") (pin "6") (pinfunction "P2_6") (pintype "bidirectional"))
      (node (ref "IC13") (pin "7") (pinfunction "P3_7") (pintype "bidirectional"))
      (node (ref "IC21") (pin "1") (pinfunction "1DE_1") (pintype "input"))
      (node (ref "IC21") (pin "12") (pinfunction "4DE_12") (pintype "input"))
      (node (ref "IC21") (pin "19") (pinfunction "~{3RE}_19") (pintype "input"))
      (node (ref "IC21") (pin "21") (pinfunction "~{4RE}_21") (pintype "input"))
      (node (ref "IC21") (pin "40") (pinfunction "~{1RE}_40") (pintype "input"))
      (node (ref "IC21") (pin "42") (pinfunction "~{2RE}_42") (pintype "input"))
      (node (ref "IC21") (pin "5") (pinfunction "2DE_5") (pintype "input"))
      (node (ref "IC21") (pin "8") (pinfunction "3DE_8") (pintype "input"))
      (node (ref "R134") (pin "2") (pinfunction "2_2") (pintype "passive"))
      (node (ref "R137") (pin "1") (pinfunction "1_1") (pintype "passive"))
      (node (ref "SW9") (pin "1") (pinfunction "1_1") (pintype "passive"))
      (node (ref "T26") (pin "1") (pinfunction "G_1") (pintype "passive"))
    )
    (net (code "4") (name "/DIR_CTRL2") (class "Default")
      (node (ref "IC13") (pin "10") (pinfunction "P5_10") (pintype "bidirectional"))
      (node (ref "IC13") (pin "11") (pinfunction "P6_11") (pintype "bidirectional"))
      (node (ref "IC13") (pin "12") (pinfunction "P7_12") (pintype "bidirectional"))
      (node (ref "IC13") (pin "9") (pinfunction "P4_9") (pintype "bidirectional"))
      (node (ref "IC9") (pin "1") (pinfunction "1DE_1") (pintype "input"))
      (node (ref "IC9") (pin "12") (pinfunction "4DE_12") (pintype "input"))
      (node (ref "IC9") (pin "19") (pinfunction "~{3RE}_19") (pintype "input"))
      (node (ref "IC9") (pin "21") (pinfunction "~{4RE}_21") (pintype "input"))
      (node (ref "IC9") (pin "40") (pinfunction "~{1RE}_40") (pintype "input"))
      (node (ref "IC9") (pin "42") (pinfunction "~{2RE}_42") (pintype "input"))
      (node (ref "IC9") (pin "5") (pinfunction "2DE_5") (pintype "input"))
      (node (ref "IC9") (pin "8") (pinfunction "3DE_8") (pintype "input"))
      (node (ref "R153") (pin "2") (pinfunction "2_2") (pintype "passive"))
      (node (ref "R156") (pin "1") (pinfunction "1_1") (pintype "passive"))
      (node (ref "SW9") (pin "2") (pinfunction "2_2") (pintype "passive"))
      (node (ref "T28") (pin "1") (pinfunction "G_1") (pintype "passive"))
    )
    (net (code "5") (name "/I2C_SCL") (class "Default")
      (node (ref "B8") (pin "1") (pinfunction "1_1") (pintype "bidirectional"))
      (node (ref "IC13") (pin "14") (pinfunction "SCL_14") (pintype "input"))
      (node (ref "IC32") (pin "1") (pinfunction "SCL_1") (pintype "input"))
      (node (ref "J37") (pin "27") (pinfunction "27_27") (pintype "bidirectional"))
    )
    (net (code "6") (name "/I2C_SDA") (class "Default")
      (node (ref "B7") (pin "1") (pinfunction "1_1") (pintype "bidirectional"))
      (node (ref "IC13") (pin "15") (pinfunction "SDA_15") (pintype "bidirectional"))
      (node (ref "IC32") (pin "3") (pinfunction "SDA_3") (pintype "bidirectional"))
      (node (ref "J37") (pin "26") (pinfunction "26_26") (pintype "bidirectional"))
    )
    (net (code "7") (name "/IO1") (class "Default")
      (node (ref "IC29") (pin "10") (pinfunction "A7_10") (pintype "bidirectional"))
      (node (ref "IC29") (pin "12") (pinfunction "A8_12") (pintype "bidirectional"))
      (node (ref "J35") (pin "4") (pinfunction "4_4") (pintype "bidirectional"))
      (node (ref "R139") (pin "2") (pinfunction "2_2") (pintype "passive"))
      (node (ref "R140") (pin "2") (pinfunction "2_2") (pintype "passive"))
    )
    (net (code "8") (name "/IO2") (class "Default")
      (node (ref "IC29") (pin "7") (pinfunction "A5_7") (pintype "bidirectional"))
      (node (ref "IC29") (pin "9") (pinfunction "A6_9") (pintype "bidirectional"))
      (node (ref "J36") (pin "4") (pinfunction "4_4") (pintype "bidirectional"))
      (node (ref "R142") (pin "2") (pinfunction "2_2") (pintype "passive"))
      (node (ref "R143") (pin "2") (pinfunction "2_2") (pintype "passive"))
    )
    (net (code "9") (name "/IO3") (class "Default")
      (node (ref "IC29") (pin "4") (pinfunction "A3_4") (pintype "bidirectional"))
      (node (ref "IC29") (pin "6") (pinfunction "A4_6") (pintype "bidirectional"))
      (node (ref "J35") (pin "2") (pinfunction "2_2") (pintype "bidirectional"))
      (node (ref "R145") (pin "2") (pinfunction "2_2") (pintype "passive"))
      (node (ref "R146") (pin "2") (pinfunction "2_2") (pintype "passive"))
    )
    (net (code "10") (name "/IO4") (class "Default")
      (node (ref "IC29") (pin "1") (pinfunction "A1_1") (pintype "bidirectional"))
      (node (ref "IC29") (pin "3") (pinfunction "A2_3") (pintype "bidirectional"))
      (node (ref "J36") (pin "2") (pinfunction "2_2") (pintype "bidirectional"))
      (node (ref "R148") (pin "2") (pinfunction "2_2") (pintype "passive"))
      (node (ref "R149") (pin "2") (pinfunction "2_2") (pintype "passive"))
    )
    (net (code "11") (name "/IO5") (class "Default")
      (node (ref "IC8") (pin "10") (pinfunction "A7_10") (pintype "bidirectional"))
      (node (ref "IC8") (pin "12") (pinfunction "A8_12") (pintype "bidirectional"))
      (node (ref "J38") (pin "4") (pinfunction "4_4") (pintype "bidirectional"))
      (node (ref "R158") (pin "2") (pinfunction "2_2") (pintype "passive"))
      (node (ref "R159") (pin "2") (pinfunction "2_2") (pintype "passive"))
    )
    (net (code "12") (name "/IO6") (class "Default")
      (node (ref "IC8") (pin "7") (pinfunction "A5_7") (pintype "bidirectional"))
      (node (ref "IC8") (pin "9") (pinfunction "A6_9") (pintype "bidirectional"))
      (node (ref "J39") (pin "4") (pinfunction "4_4") (pintype "bidirectional"))
      (node (ref "R161") (pin "2") (pinfunction "2_2") (pintype "passive"))
      (node (ref "R162") (pin "2") (pinfunction "2_2") (pintype "passive"))
    )
    (net (code "13") (name "/IO7") (class "Default")
      (node (ref "IC8") (pin "4") (pinfunction "A3_4") (pintype "bidirectional"))
      (node (ref "IC8") (pin "6") (pinfunction "A4_6") (pintype "bidirectional"))
      (node (ref "J38") (pin "2") (pinfunction "2_2") (pintype "bidirectional"))
      (node (ref "R164") (pin "2") (pinfunction "2_2") (pintype "passive"))
      (node (ref "R165") (pin "2") (pinfunction "2_2") (pintype "passive"))
    )
    (net (code "14") (name "/IO8") (class "Default")
      (node (ref "IC8") (pin "1") (pinfunction "A1_1") (pintype "bidirectional"))
      (node (ref "IC8") (pin "3") (pinfunction "A2_3") (pintype "bidirectional"))
      (node (ref "J39") (pin "2") (pinfunction "2_2") (pintype "bidirectional"))
      (node (ref "R168") (pin "2") (pinfunction "2_2") (pintype "passive"))
      (node (ref "R169") (pin "2") (pinfunction "2_2") (pintype "passive"))
    )
    (net (code "15") (name "/LVDS1_N") (class "Default")
      (node (ref "IC21") (pin "48") (pinfunction "1B_48") (pintype "bidirectional"))
      (node (ref "J37") (pin "3") (pinfunction "3_3") (pintype "bidirectional"))
      (node (ref "R141") (pin "2") (pinfunction "2_2") (pintype "passive"))
    )
    (net (code "16") (name "/LVDS1_P") (class "Default")
      (node (ref "IC21") (pin "47") (pinfunction "1A_47") (pintype "bidirectional"))
      (node (ref "J37") (pin "2") (pinfunction "2_2") (pintype "bidirectional"))
      (node (ref "R141") (pin "1") (pinfunction "1_1") (pintype "passive"))
    )
    (net (code "17") (name "/LVDS2_N") (class "Default")
      (node (ref "IC21") (pin "4") (pinfunction "2B_4") (pintype "bidirectional"))
      (node (ref "J37") (pin "6") (pinfunction "6_6") (pintype "bidirectional"))
      (node (ref "R144") (pin "2") (pinfunction "2_2") (pintype "passive"))
    )
    (net (code "18") (name "/LVDS2_P") (class "Default")
      (node (ref "IC21") (pin "3") (pinfunction "2A_3") (pintype "bidirectional"))
      (node (ref "J37") (pin "5") (pinfunction "5_5") (pintype "bidirectional"))
      (node (ref "R144") (pin "1") (pinfunction "1_1") (pintype "passive"))
    )
    (net (code "19") (name "/LVDS3_N") (class "Default")
      (node (ref "IC21") (pin "10") (pinfunction "3B_10") (pintype "bidirectional"))
      (node (ref "J37") (pin "9") (pinfunction "9_9") (pintype "bidirectional"))
      (node (ref "R147") (pin "2") (pinfunction "2_2") (pintype "passive"))
    )
    (net (code "20") (name "/LVDS3_P") (class "Default")
      (node (ref "IC21") (pin "9") (pinfunction "3A_9") (pintype "bidirectional"))
      (node (ref "J37") (pin "8") (pinfunction "8_8") (pintype "bidirectional"))
      (node (ref "R147") (pin "1") (pinfunction "1_1") (pintype "passive"))
    )
    (net (code "21") (name "/LVDS4_N") (class "Default")
      (node (ref "IC21") (pin "14") (pinfunction "4B_14") (pintype "bidirectional"))
      (node (ref "J37") (pin "12") (pinfunction "12_12") (pintype "bidirectional"))
      (node (ref "R151") (pin "2") (pinfunction "2_2") (pintype "passive"))
    )
    (net (code "22") (name "/LVDS4_P") (class "Default")
      (node (ref "IC21") (pin "13") (pinfunction "4A_13") (pintype "bidirectional"))
      (node (ref "J37") (pin "11") (pinfunction "11_11") (pintype "bidirectional"))
      (node (ref "R151") (pin "1") (pinfunction "1_1") (pintype "passive"))
    )
    (net (code "23") (name "/LVDS5_N") (class "Default")
      (node (ref "IC9") (pin "48") (pinfunction "1B_48") (pintype "bidirectional"))
      (node (ref "J37") (pin "15") (pinfunction "15_15") (pintype "bidirectional"))
      (node (ref "R160") (pin "2") (pinfunction "2_2") (pintype "passive"))
    )
    (net (code "24") (name "/LVDS5_P") (class "Default")
      (node (ref "IC9") (pin "47") (pinfunction "1A_47") (pintype "bidirectional"))
      (node (ref "J37") (pin "14") (pinfunction "14_14") (pintype "bidirectional"))
      (node (ref "R160") (pin "1") (pinfunction "1_1") (pintype "passive"))
    )
    (net (code "25") (name "/LVDS6_N") (class "Default")
      (node (ref "IC9") (pin "4") (pinfunction "2B_4") (pintype "bidirectional"))
      (node (ref "J37") (pin "18") (pinfunction "18_18") (pintype "bidirectional"))
      (node (ref "R163") (pin "2") (pinfunction "2_2") (pintype "passive"))
    )
    (net (code "26") (name "/LVDS6_P") (class "Default")
      (node (ref "IC9") (pin "3") (pinfunction "2A_3") (pintype "bidirectional"))
      (node (ref "J37") (pin "17") (pinfunction "17_17") (pintype "bidirectional"))
      (node (ref "R163") (pin "1") (pinfunction "1_1") (pintype "passive"))
    )
    (net (code "27") (name "/LVDS7_N") (class "Default")
      (node (ref "IC9") (pin "10") (pinfunction "3B_10") (pintype "bidirectional"))
      (node (ref "J37") (pin "21") (pinfunction "21_21") (pintype "bidirectional"))
      (node (ref "R166") (pin "2") (pinfunction "2_2") (pintype "passive"))
    )
    (net (code "28") (name "/LVDS7_P") (class "Default")
      (node (ref "IC9") (pin "9") (pinfunction "3A_9") (pintype "bidirectional"))
      (node (ref "J37") (pin "20") (pinfunction "20_20") (pintype "bidirectional"))
      (node (ref "R166") (pin "1") (pinfunction "1_1") (pintype "passive"))
    )
    (net (code "29") (name "/LVDS8_N") (class "Default")
      (node (ref "IC9") (pin "14") (pinfunction "4B_14") (pintype "bidirectional"))
      (node (ref "J37") (pin "24") (pinfunction "24_24") (pintype "bidirectional"))
      (node (ref "R170") (pin "2") (pinfunction "2_2") (pintype "passive"))
    )
    (net (code "30") (name "/LVDS8_P") (class "Default")
      (node (ref "IC9") (pin "13") (pinfunction "4A_13") (pintype "bidirectional"))
      (node (ref "J37") (pin "23") (pinfunction "23_23") (pintype "bidirectional"))
      (node (ref "R170") (pin "1") (pinfunction "1_1") (pintype "passive"))
    )
    (net (code "31") (name "/TERM_IO1") (class "Default")
      (node (ref "R1") (pin "1") (pinfunction "1_1") (pintype "passive"))
      (node (ref "SW1") (pin "8") (pinfunction "8_8") (pintype "passive"))
      (node (ref "T1") (pin "1") (pinfunction "G_1") (pintype "passive"))
    )
    (net (code "32") (name "/TERM_IO2") (class "Default")
      (node (ref "R2") (pin "1") (pinfunction "1_1") (pintype "passive"))
      (node (ref "SW1") (pin "7") (pinfunction "7_7") (pintype "passive"))
      (node (ref "T2") (pin "1") (pinfunction "G_1") (pintype "passive"))
    )
    (net (code "33") (name "/TERM_IO3") (class "Default")
      (node (ref "R3") (pin "1") (pinfunction "1_1") (pintype "passive"))
      (node (ref "SW1") (pin "6") (pinfunction "6_6") (pintype "passive"))
      (node (ref "T3") (pin "1") (pinfunction "G_1") (pintype "passive"))
    )
    (net (code "34") (name "/TERM_IO4") (class "Default")
      (node (ref "R4") (pin "1") (pinfunction "1_1") (pintype "passive"))
      (node (ref "SW1") (pin "5") (pinfunction "5_5") (pintype "passive"))
      (node (ref "T4") (pin "1") (pinfunction "G_1") (pintype "passive"))
    )
    (net (code "35") (name "/TERM_IO5") (class "Default")
      (node (ref "R5") (pin "1") (pinfunction "1_1") (pintype "passive"))
      (node (ref "SW2") (pin "8") (pinfunction "8_8") (pintype "passive"))
      (node (ref "T5") (pin "1") (pinfunction "G_1") (pintype "passive"))
    )
    (net (code "36") (name "/TERM_IO6") (class "Default")
      (node (ref "R7") (pin "1") (pinfunction "1_1") (pintype "passive"))
      (node (ref "SW2") (pin "7") (pinfunction "7_7") (pintype "passive"))
      (node (ref "T6") (pin "1") (pinfunction "G_1") (pintype "passive"))
    )
    (net (code "37") (name "/TERM_IO7") (class "Default")
      (node (ref "R9") (pin "1") (pinfunction "1_1") (pintype "passive"))
      (node (ref "SW2") (pin "6") (pinfunction "6_6") (pintype "passive"))
      (node (ref "T7") (pin "1") (pinfunction "G_1") (pintype "passive"))
    )
    (net (code "38") (name "/TERM_IO8") (class "Default")
      (node (ref "R11") (pin "1") (pinfunction "1_1") (pintype "passive"))
      (node (ref "SW2") (pin "5") (pinfunction "5_5") (pintype "passive"))
      (node (ref "T8") (pin "1") (pinfunction "G_1") (pintype "passive"))
    )
    (net (code "39") (name "GND") (class "Default")
      (node (ref "B1") (pin "1") (pinfunction "1_1") (pintype "bidirectional"))
      (node (ref "B2") (pin "1") (pinfunction "1_1") (pintype "bidirectional"))
      (node (ref "B4") (pin "1") (pinfunction "1_1") (pintype "bidirectional"))
      (node (ref "C14") (pin "1") (pinfunction "1_1") (pintype "passive"))
      (node (ref "C15") (pin "1") (pinfunction "1_1") (pintype "passive"))
      (node (ref "C16") (pin "1") (pinfunction "1_1") (pintype "passive"))
      (node (ref "C17") (pin "1") (pinfunction "1_1") (pintype "passive"))
      (node (ref "C18") (pin "2") (pinfunction "2_2") (pintype "passive"))
      (node (ref "C19") (pin "1") (pinfunction "1_1") (pintype "passive"))
      (node (ref "C20") (pin "1") (pinfunction "1_1") (pintype "passive"))
      (node (ref "C21") (pin "1") (pinfunction "1_1") (pintype "passive"))
      (node (ref "C22") (pin "1") (pinfunction "1_1") (pintype "passive"))
      (node (ref "C23") (pin "1") (pinfunction "1_1") (pintype "passive"))
      (node (ref "C24") (pin "1") (pinfunction "1_1") (pintype "passive"))
      (node (ref "C33") (pin "1") (pinfunction "1_1") (pintype "passive"))
      (node (ref "C34") (pin "2") (pinfunction "2_2") (pintype "passive"))
      (node (ref "C35") (pin "1") (pinfunction "1_1") (pintype "passive"))
      (node (ref "C36") (pin "2") (pinfunction "2_2") (pintype "passive"))
      (node (ref "C37") (pin "1") (pinfunction "1_1") (pintype "passive"))
      (node (ref "C38") (pin "1") (pinfunction "1_1") (pintype "passive"))
      (node (ref "C53") (pin "1") (pinfunction "1_1") (pintype "passive"))
      (node (ref "C54") (pin "1") (pinfunction "1_1") (pintype "passive"))
      (node (ref "C55") (pin "1") (pinfunction "1_1") (pintype "passive"))
      (node (ref "C56") (pin "1") (pinfunction "1_1") (pintype "passive"))
      (node (ref "C69") (pin "1") (pinfunction "1_1") (pintype "passive"))
      (node (ref "C70") (pin "1") (pinfunction "1_1") (pintype "passive"))
      (node (ref "C71") (pin "2") (pinfunction "2_2") (pintype "passive"))
      (node (ref "C72") (pin "1") (pinfunction "1_1") (pintype "passive"))
      (node (ref "C73") (pin "1") (pinfunction "1_1") (pintype "passive"))
      (node (ref "C74") (pin "1") (pinfunction "1_1") (pintype "passive"))
      (node (ref "C75") (pin "1") (pinfunction "1_1") (pintype "passive"))
      (node (ref "IC1") (pin "1") (pinfunction "-Vin_1") (pintype "power_in"))
      (node (ref "IC10") (pin "9") (pinfunction "GND2_9") (pintype "power_in"))
      (node (ref "IC11") (pin "8") (pinfunction "GND1_8") (pintype "power_in"))
      (node (ref "IC12") (pin "2") (pinfunction "-Vin_2") (pintype "power_in"))
      (node (ref "IC13") (pin "1") (pinfunction "A0_1") (pintype "input"))
      (node (ref "IC13") (pin "8") (pinfunction "GND_8") (pintype "power_in"))
      (node (ref "IC2") (pin "1") (pinfunction "-Vin_1") (pintype "power_in"))
      (node (ref "IC21") (pin "18") (pinfunction "GND_18") (pintype "power_in"))
      (node (ref "IC21") (pin "23") (pinfunction "GND_23") (pintype "power_in"))
      (node (ref "IC21") (pin "27") (pinfunction "GND_27") (pintype "power_in"))
      (node (ref "IC21") (pin "31") (pinfunction "GND_31") (pintype "power_in"))
      (node (ref "IC21") (pin "34") (pinfunction "GND_34") (pintype "power_in"))
      (node (ref "IC21") (pin "38") (pinfunction "GND_38") (pintype "power_in"))
      (node (ref "IC21") (pin "43") (pinfunction "GND_43") (pintype "power_in"))
      (node (ref "IC21") (pin "49") (pinfunction "EP_49") (pintype "power_in"))
      (node (ref "IC21") (pin "6") (pinfunction "GND_6") (pintype "power_in"))
      (node (ref "IC21") (pin "7") (pinfunction "GND_7") (pintype "power_in"))
      (node (ref "IC22") (pin "9") (pinfunction "GND2_9") (pintype "power_in"))
      (node (ref "IC28") (pin "8") (pinfunction "GND1_8") (pintype "power_in"))
      (node (ref "IC30") (pin "1") (pinfunction "PGND_1") (pintype "power_in"))
      (node (ref "IC30") (pin "11") (pinfunction "EP_11") (pintype "power_in"))
      (node (ref "IC30") (pin "6") (pinfunction "AGND_6") (pintype "power_in"))
      (node (ref "IC31") (pin "2") (pinfunction "-Vin_2") (pintype "power_in"))
      (node (ref "IC32") (pin "2") (pinfunction "VSS_2") (pintype "power_in"))
      (node (ref "IC9") (pin "18") (pinfunction "GND_18") (pintype "power_in"))
      (node (ref "IC9") (pin "23") (pinfunction "GND_23") (pintype "power_in"))
      (node (ref "IC9") (pin "27") (pinfunction "GND_27") (pintype "power_in"))
      (node (ref "IC9") (pin "31") (pinfunction "GND_31") (pintype "power_in"))
      (node (ref "IC9") (pin "34") (pinfunction "GND_34") (pintype "power_in"))
      (node (ref "IC9") (pin "38") (pinfunction "GND_38") (pintype "power_in"))
      (node (ref "IC9") (pin "43") (pinfunction "GND_43") (pintype "power_in"))
      (node (ref "IC9") (pin "49") (pinfunction "EP_49") (pintype "power_in"))
      (node (ref "IC9") (pin "6") (pinfunction "GND_6") (pintype "power_in"))
      (node (ref "IC9") (pin "7") (pinfunction "GND_7") (pintype "power_in"))
      (node (ref "J37") (pin "1") (pinfunction "1_1") (pintype "bidirectional"))
      (node (ref "J37") (pin "10") (pinfunction "10_10") (pintype "bidirectional"))
      (node (ref "J37") (pin "13") (pinfunction "13_13") (pintype "bidirectional"))
      (node (ref "J37") (pin "16") (pinfunction "16_16") (pintype "bidirectional"))
      (node (ref "J37") (pin "19") (pinfunction "19_19") (pintype "bidirectional"))
      (node (ref "J37") (pin "22") (pinfunction "22_22") (pintype "bidirectional"))
      (node (ref "J37") (pin "25") (pinfunction "25_25") (pintype "bidirectional"))
      (node (ref "J37") (pin "4") (pinfunction "4_4") (pintype "bidirectional"))
      (node (ref "J37") (pin "7") (pinfunction "7_7") (pintype "bidirectional"))
      (node (ref "LD4") (pin "1") (pinfunction "C_1") (pintype "passive"))
      (node (ref "LD7") (pin "1") (pinfunction "C_1") (pintype "passive"))
      (node (ref "LD9") (pin "1") (pinfunction "C_1") (pintype "passive"))
      (node (ref "R138") (pin "2") (pinfunction "2_2") (pintype "passive"))
      (node (ref "R152") (pin "2") (pinfunction "2_2") (pintype "passive"))
      (node (ref "R157") (pin "2") (pinfunction "2_2") (pintype "passive"))
      (node (ref "R171") (pin "2") (pinfunction "2_2") (pintype "passive"))
      (node (ref "R173") (pin "1") (pinfunction "1_1") (pintype "passive"))
      (node (ref "SW9") (pin "3") (pinfunction "3_3") (pintype "passive"))
      (node (ref "SW9") (pin "4") (pinfunction "4_4") (pintype "passive"))
      (node (ref "T26") (pin "2") (pinfunction "S_2") (pintype "passive"))
      (node (ref "T28") (pin "2") (pinfunction "S_2") (pintype "passive"))
    )
    (net (code "40") (name "GND_ISO1") (class "Default")
      (node (ref "B10") (pin "1") (pinfunction "1_1") (pintype "bidirectional"))
      (node (ref "C48") (pin "1") (pinfunction "1_1") (pintype "passive"))
      (node (ref "C49") (pin "1") (pinfunction "1_1") (pintype "passive"))
      (node (ref "C50") (pin "1") (pinfunction "1_1") (pintype "passive"))
      (node (ref "C51") (pin "1") (pinfunction "1_1") (pintype "passive"))
      (node (ref "C52") (pin "2") (pinfunction "2_2") (pintype "passive"))
      (node (ref "IC2") (pin "7") (pinfunction "-Vout_7") (pintype "power_in"))
      (node (ref "IC22") (pin "8") (pinfunction "GND1_8") (pintype "power_in"))
      (node (ref "IC28") (pin "9") (pinfunction "GND2_9") (pintype "power_in"))
      (node (ref "IC29") (pin "11") (pinfunction "GND_11") (pintype "power_in"))
      (node (ref "IC29") (pin "13") (pinfunction "OE_13") (pintype "input"))
      (node (ref "IC29") (pin "2") (pinfunction "GND_2") (pintype "power_in"))
      (node (ref "IC29") (pin "5") (pinfunction "GND_5") (pintype "power_in"))
      (node (ref "IC29") (pin "8") (pinfunction "GND_8") (pintype "power_in"))
      (node (ref "IC31") (pin "4") (pinfunction "-Vout_4") (pintype "power_in"))
      (node (ref "J35") (pin "1") (pinfunction "1_1") (pintype "bidirectional"))
      (node (ref "J35") (pin "3") (pinfunction "3_3") (pintype "bidirectional"))
      (node (ref "J36") (pin "1") (pinfunction "1_1") (pintype "bidirectional"))
      (node (ref "J36") (pin "3") (pinfunction "3_3") (pintype "bidirectional"))
      (node (ref "LD1") (pin "1") (pinfunction "C_1") (pintype "passive"))
      (node (ref "LD1") (pin "3") (pinfunction "C_3") (pintype "passive"))
      (node (ref "LD2") (pin "1") (pinfunction "C_1") (pintype "passive"))
      (node (ref "LD2") (pin "3") (pinfunction "C_3") (pintype "passive"))
      (node (ref "R140") (pin "1") (pinfunction "1_1") (pintype "passive"))
      (node (ref "R143") (pin "1") (pinfunction "1_1") (pintype "passive"))
      (node (ref "R146") (pin "1") (pinfunction "1_1") (pintype "passive"))
      (node (ref "R149") (pin "1") (pinfunction "1_1") (pintype "passive"))
      (node (ref "T1") (pin "2") (pinfunction "S_2") (pintype "passive"))
      (node (ref "T2") (pin "2") (pinfunction "S_2") (pintype "passive"))
      (node (ref "T27") (pin "2") (pinfunction "S_2") (pintype "passive"))
      (node (ref "T3") (pin "2") (pinfunction "S_2") (pintype "passive"))
      (node (ref "T4") (pin "2") (pinfunction "S_2") (pintype "passive"))
    )
    (net (code "41") (name "GND_ISO2") (class "Default")
      (node (ref "B12") (pin "1") (pinfunction "1_1") (pintype "bidirectional"))
      (node (ref "C28") (pin "1") (pinfunction "1_1") (pintype "passive"))
      (node (ref "C29") (pin "1") (pinfunction "1_1") (pintype "passive"))
      (node (ref "C30") (pin "1") (pinfunction "1_1") (pintype "passive"))
      (node (ref "C31") (pin "1") (pinfunction "1_1") (pintype "passive"))
      (node (ref "C32") (pin "2") (pinfunction "2_2") (pintype "passive"))
      (node (ref "IC1") (pin "7") (pinfunction "-Vout_7") (pintype "power_in"))
      (node (ref "IC10") (pin "8") (pinfunction "GND1_8") (pintype "power_in"))
      (node (ref "IC11") (pin "9") (pinfunction "GND2_9") (pintype "power_in"))
      (node (ref "IC12") (pin "4") (pinfunction "-Vout_4") (pintype "power_in"))
      (node (ref "IC8") (pin "11") (pinfunction "GND_11") (pintype "power_in"))
      (node (ref "IC8") (pin "13") (pinfunction "OE_13") (pintype "input"))
      (node (ref "IC8") (pin "2") (pinfunction "GND_2") (pintype "power_in"))
      (node (ref "IC8") (pin "5") (pinfunction "GND_5") (pintype "power_in"))
      (node (ref "IC8") (pin "8") (pinfunction "GND_8") (pintype "power_in"))
      (node (ref "J38") (pin "1") (pinfunction "1_1") (pintype "bidirectional"))
      (node (ref "J38") (pin "3") (pinfunction "3_3") (pintype "bidirectional"))
      (node (ref "J39") (pin "1") (pinfunction "1_1") (pintype "bidirectional"))
      (node (ref "J39") (pin "3") (pinfunction "3_3") (pintype "bidirectional"))
      (node (ref "LD3") (pin "1") (pinfunction "C_1") (pintype "passive"))
      (node (ref "LD3") (pin "3") (pinfunction "C_3") (pintype "passive"))
      (node (ref "LD8") (pin "1") (pinfunction "C_1") (pintype "passive"))
      (node (ref "LD8") (pin "3") (pinfunction "C_3") (pintype "passive"))
      (node (ref "R159") (pin "1") (pinfunction "1_1") (pintype "passive"))
      (node (ref "R162") (pin "1") (pinfunction "1_1") (pintype "passive"))
      (node (ref "R165") (pin "1") (pinfunction "1_1") (pintype "passive"))
      (node (ref "R169") (pin "1") (pinfunction "1_1") (pintype "passive"))
      (node (ref "T29") (pin "2") (pinfunction "S_2") (pintype "passive"))
      (node (ref "T5") (pin "2") (pinfunction "S_2") (pintype "passive"))
      (node (ref "T6") (pin "2") (pinfunction "S_2") (pintype "passive"))
      (node (ref "T7") (pin "2") (pinfunction "S_2") (pintype "passive"))
      (node (ref "T8") (pin "2") (pinfunction "S_2") (pintype "passive"))
    )
    (net (code "42") (name "Net-(IC8-DIR)") (class "Default")
      (node (ref "IC8") (pin "24") (pinfunction "DIR_24") (pintype "input"))
      (node (ref "R172") (pin "1") (pinfunction "1_1") (pintype "passive"))
      (node (ref "T29") (pin "3") (pinfunction "D_3") (pintype "passive"))
    )
    (net (code "43") (name "Net-(IC9-1FSEN)") (class "Default")
      (node (ref "IC9") (pin "20") (pinfunction "3FSEN_20") (pintype "input"))
      (node (ref "IC9") (pin "22") (pinfunction "4FSEN_22") (pintype "input"))
      (node (ref "IC9") (pin "39") (pinfunction "1FSEN_39") (pintype "input"))
      (node (ref "IC9") (pin "41") (pinfunction "2FSEN_41") (pintype "input"))
      (node (ref "R157") (pin "1") (pinfunction "1_1") (pintype "passive"))
      (node (ref "R171") (pin "1") (pinfunction "1_1") (pintype "passive"))
    )
    (net (code "44") (name "Net-(IC10-A1)") (class "Default")
      (node (ref "IC10") (pin "2") (pinfunction "A1_2") (pintype "input"))
      (node (ref "IC11") (pin "15") (pinfunction "B1_15") (pintype "output"))
      (node (ref "IC8") (pin "14") (pinfunction "B8_14") (pintype "bidirectional"))
      (node (ref "IC8") (pin "15") (pinfunction "B7_15") (pintype "bidirectional"))
    )
    (net (code "45") (name "Net-(IC10-A2)") (class "Default")
      (node (ref "IC10") (pin "3") (pinfunction "A2_3") (pintype "input"))
      (node (ref "IC11") (pin "14") (pinfunction "B2_14") (pintype "output"))
      (node (ref "IC8") (pin "17") (pinfunction "B6_17") (pintype "bidirectional"))
      (node (ref "IC8") (pin "18") (pinfunction "B5_18") (pintype "bidirectional"))
    )
    (net (code "46") (name "Net-(IC10-A3)") (class "Default")
      (node (ref "IC10") (pin "4") (pinfunction "A3_4") (pintype "input"))
      (node (ref "IC11") (pin "13") (pinfunction "B3_13") (pintype "output"))
      (node (ref "IC8") (pin "19") (pinfunction "B4_19") (pintype "bidirectional"))
      (node (ref "IC8") (pin "20") (pinfunction "B3_20") (pintype "bidirectional"))
    )
    (net (code "47") (name "Net-(IC10-A4)") (class "Default")
      (node (ref "IC10") (pin "5") (pinfunction "A4_5") (pintype "input"))
      (node (ref "IC11") (pin "12") (pinfunction "B4_12") (pintype "output"))
      (node (ref "IC8") (pin "22") (pinfunction "B2_22") (pintype "bidirectional"))
      (node (ref "IC8") (pin "23") (pinfunction "B1_23") (pintype "bidirectional"))
    )
    (net (code "48") (name "Net-(IC10-A5)") (class "Default")
      (node (ref "IC10") (pin "6") (pinfunction "A5_6") (pintype "output"))
      (node (ref "IC11") (pin "11") (pinfunction "B5_11") (pintype "input"))
      (node (ref "T29") (pin "1") (pinfunction "G_1") (pintype "passive"))
    )
    (net (code "49") (name "Net-(IC10-B1)") (class "Default")
      (node (ref "IC10") (pin "15") (pinfunction "B1_15") (pintype "output"))
      (node (ref "IC9") (pin "35") (pinfunction "1D_35") (pintype "input"))
    )
    (net (code "50") (name "Net-(IC10-B2)") (class "Default")
      (node (ref "IC10") (pin "14") (pinfunction "B2_14") (pintype "output"))
      (node (ref "IC9") (pin "32") (pinfunction "2D_32") (pintype "input"))
    )
    (net (code "51") (name "Net-(IC10-B3)") (class "Default")
      (node (ref "IC10") (pin "13") (pinfunction "B3_13") (pintype "output"))
      (node (ref "IC9") (pin "28") (pinfunction "3D_28") (pintype "input"))
    )
    (net (code "52") (name "Net-(IC10-B4)") (class "Default")
      (node (ref "IC10") (pin "12") (pinfunction "B4_12") (pintype "output"))
      (node (ref "IC9") (pin "25") (pinfunction "4D_25") (pintype "input"))
    )
    (net (code "53") (name "Net-(IC10-B5)") (class "Default")
      (node (ref "IC10") (pin "11") (pinfunction "B5_11") (pintype "input"))
      (node (ref "R154") (pin "2") (pinfunction "2_2") (pintype "passive"))
      (node (ref "R155") (pin "1") (pinfunction "1_1") (pintype "passive"))
      (node (ref "T28") (pin "3") (pinfunction "D_3") (pintype "passive"))
    )
    (net (code "54") (name "Net-(IC11-A1)") (class "Default")
      (node (ref "IC11") (pin "2") (pinfunction "A1_2") (pintype "input"))
      (node (ref "IC9") (pin "36") (pinfunction "1R_36") (pintype "output"))
    )
    (net (code "55") (name "Net-(IC11-A2)") (class "Default")
      (node (ref "IC11") (pin "3") (pinfunction "A2_3") (pintype "input"))
      (node (ref "IC9") (pin "33") (pinfunction "2R_33") (pintype "output"))
    )
    (net (code "56") (name "Net-(IC11-A3)") (class "Default")
      (node (ref "IC11") (pin "4") (pinfunction "A3_4") (pintype "input"))
      (node (ref "IC9") (pin "29") (pinfunction "3R_29") (pintype "output"))
    )
    (net (code "57") (name "Net-(IC11-A4)") (class "Default")
      (node (ref "IC11") (pin "5") (pinfunction "A4_5") (pintype "input"))
      (node (ref "IC9") (pin "26") (pinfunction "4R_26") (pintype "output"))
    )
    (net (code "58") (name "Net-(IC21-1D)") (class "Default")
      (node (ref "IC21") (pin "35") (pinfunction "1D_35") (pintype "input"))
      (node (ref "IC22") (pin "15") (pinfunction "B1_15") (pintype "output"))
    )
    (net (code "59") (name "Net-(IC21-1FSEN)") (class "Default")
      (node (ref "IC21") (pin "20") (pinfunction "3FSEN_20") (pintype "input"))
      (node (ref "IC21") (pin "22") (pinfunction "4FSEN_22") (pintype "input"))
      (node (ref "IC21") (pin "39") (pinfunction "1FSEN_39") (pintype "input"))
      (node (ref "IC21") (pin "41") (pinfunction "2FSEN_41") (pintype "input"))
      (node (ref "R138") (pin "1") (pinfunction "1_1") (pintype "passive"))
      (node (ref "R152") (pin "1") (pinfunction "1_1") (pintype "passive"))
    )
    (net (code "60") (name "Net-(IC21-1R)") (class "Default")
      (node (ref "IC21") (pin "36") (pinfunction "1R_36") (pintype "output"))
      (node (ref "IC28") (pin "2") (pinfunction "A1_2") (pintype "input"))
    )
    (net (code "61") (name "Net-(IC21-2D)") (class "Default")
      (node (ref "IC21") (pin "32") (pinfunction "2D_32") (pintype "input"))
      (node (ref "IC22") (pin "14") (pinfunction "B2_14") (pintype "output"))
    )
    (net (code "62") (name "Net-(IC21-2R)") (class "Default")
      (node (ref "IC21") (pin "33") (pinfunction "2R_33") (pintype "output"))
      (node (ref "IC28") (pin "3") (pinfunction "A2_3") (pintype "input"))
    )
    (net (code "63") (name "Net-(IC21-3D)") (class "Default")
      (node (ref "IC21") (pin "28") (pinfunction "3D_28") (pintype "input"))
      (node (ref "IC22") (pin "13") (pinfunction "B3_13") (pintype "output"))
    )
    (net (code "64") (name "Net-(IC21-3R)") (class "Default")
      (node (ref "IC21") (pin "29") (pinfunction "3R_29") (pintype "output"))
      (node (ref "IC28") (pin "4") (pinfunction "A3_4") (pintype "input"))
    )
    (net (code "65") (name "Net-(IC21-4D)") (class "Default")
      (node (ref "IC21") (pin "25") (pinfunction "4D_25") (pintype "input"))
      (node (ref "IC22") (pin "12") (pinfunction "B4_12") (pintype "output"))
    )
    (net (code "66") (name "Net-(IC21-4R)") (class "Default")
      (node (ref "IC21") (pin "26") (pinfunction "4R_26") (pintype "output"))
      (node (ref "IC28") (pin "5") (pinfunction "A4_5") (pintype "input"))
    )
    (net (code "67") (name "Net-(IC22-A1)") (class "Default")
      (node (ref "IC22") (pin "2") (pinfunction "A1_2") (pintype "input"))
      (node (ref "IC28") (pin "15") (pinfunction "B1_15") (pintype "output"))
      (node (ref "IC29") (pin "14") (pinfunction "B8_14") (pintype "bidirectional"))
      (node (ref "IC29") (pin "15") (pinfunction "B7_15") (pintype "bidirectional"))
    )
    (net (code "68") (name "Net-(IC22-A2)") (class "Default")
      (node (ref "IC22") (pin "3") (pinfunction "A2_3") (pintype "input"))
      (node (ref "IC28") (pin "14") (pinfunction "B2_14") (pintype "output"))
      (node (ref "IC29") (pin "17") (pinfunction "B6_17") (pintype "bidirectional"))
      (node (ref "IC29") (pin "18") (pinfunction "B5_18") (pintype "bidirectional"))
    )
    (net (code "69") (name "Net-(IC22-A3)") (class "Default")
      (node (ref "IC22") (pin "4") (pinfunction "A3_4") (pintype "input"))
      (node (ref "IC28") (pin "13") (pinfunction "B3_13") (pintype "output"))
      (node (ref "IC29") (pin "19") (pinfunction "B4_19") (pintype "bidirectional"))
      (node (ref "IC29") (pin "20") (pinfunction "B3_20") (pintype "bidirectional"))
    )
    (net (code "70") (name "Net-(IC22-A4)") (class "Default")
      (node (ref "IC22") (pin "5") (pinfunction "A4_5") (pintype "input"))
      (node (ref "IC28") (pin "12") (pinfunction "B4_12") (pintype "output"))
      (node (ref "IC29") (pin "22") (pinfunction "B2_22") (pintype "bidirectional"))
      (node (ref "IC29") (pin "23") (pinfunction "B1_23") (pintype "bidirectional"))
    )
    (net (code "71") (name "Net-(IC22-A5)") (class "Default")
      (node (ref "IC22") (pin "6") (pinfunction "A5_6") (pintype "output"))
      (node (ref "IC28") (pin "11") (pinfunction "B5_11") (pintype "input"))
      (node (ref "T27") (pin "1") (pinfunction "G_1") (pintype "passive"))
    )
    (net (code "72") (name "Net-(IC22-B5)") (class "Default")
      (node (ref "IC22") (pin "11") (pinfunction "B5_11") (pintype "input"))
      (node (ref "R135") (pin "2") (pinfunction "2_2") (pintype "passive"))
      (node (ref "R136") (pin "1") (pinfunction "1_1") (pintype "passive"))
      (node (ref "T26") (pin "3") (pinfunction "D_3") (pintype "passive"))
    )
    (net (code "73") (name "Net-(IC29-DIR)") (class "Default")
      (node (ref "IC29") (pin "24") (pinfunction "DIR_24") (pintype "input"))
      (node (ref "R150") (pin "1") (pinfunction "1_1") (pintype "passive"))
      (node (ref "T27") (pin "3") (pinfunction "D_3") (pintype "passive"))
    )
    (net (code "74") (name "Net-(IC30-FB)") (class "Default")
      (node (ref "IC30") (pin "5") (pinfunction "FB_5") (pintype "input"))
      (node (ref "R167") (pin "1") (pinfunction "1_1") (pintype "passive"))
      (node (ref "R173") (pin "2") (pinfunction "2_2") (pintype "passive"))
    )
    (net (code "75") (name "Net-(IC30-SW)") (class "Default")
      (node (ref "IC30") (pin "9") (pinfunction "SW_9") (pintype "output"))
      (node (ref "L1") (pin "1") (pinfunction "1_1") (pintype "passive"))
    )
    (net (code "76") (name "Net-(LD1A-A)") (class "Default")
      (node (ref "LD1") (pin "2") (pinfunction "A_2") (pintype "passive"))
      (node (ref "R1") (pin "2") (pinfunction "2_2") (pintype "passive"))
    )
    (net (code "77") (name "Net-(LD1B-A)") (class "Default")
      (node (ref "LD1") (pin "4") (pinfunction "A_4") (pintype "passive"))
      (node (ref "R3") (pin "2") (pinfunction "2_2") (pintype "passive"))
    )
    (net (code "78") (name "Net-(LD2A-A)") (class "Default")
      (node (ref "LD2") (pin "2") (pinfunction "A_2") (pintype "passive"))
      (node (ref "R2") (pin "2") (pinfunction "2_2") (pintype "passive"))
    )
    (net (code "79") (name "Net-(LD2B-A)") (class "Default")
      (node (ref "LD2") (pin "4") (pinfunction "A_4") (pintype "passive"))
      (node (ref "R4") (pin "2") (pinfunction "2_2") (pintype "passive"))
    )
    (net (code "80") (name "Net-(LD3A-A)") (class "Default")
      (node (ref "LD3") (pin "2") (pinfunction "A_2") (pintype "passive"))
      (node (ref "R5") (pin "2") (pinfunction "2_2") (pintype "passive"))
    )
    (net (code "81") (name "Net-(LD3B-A)") (class "Default")
      (node (ref "LD3") (pin "4") (pinfunction "A_4") (pintype "passive"))
      (node (ref "R9") (pin "2") (pinfunction "2_2") (pintype "passive"))
    )
    (net (code "82") (name "Net-(LD4-A)") (class "Default")
      (node (ref "LD4") (pin "2") (pinfunction "A_2") (pintype "passive"))
      (node (ref "R6") (pin "1") (pinfunction "1_1") (pintype "passive"))
    )
    (net (code "83") (name "Net-(LD5A-C)") (class "Default")
      (node (ref "LD5") (pin "1") (pinfunction "C_1") (pintype "passive"))
      (node (ref "R134") (pin "1") (pinfunction "1_1") (pintype "passive"))
    )
    (net (code "84") (name "Net-(LD5B-C)") (class "Default")
      (node (ref "LD5") (pin "3") (pinfunction "C_3") (pintype "passive"))
      (node (ref "R135") (pin "1") (pinfunction "1_1") (pintype "passive"))
    )
    (net (code "85") (name "Net-(LD6A-C)") (class "Default")
      (node (ref "LD6") (pin "1") (pinfunction "C_1") (pintype "passive"))
      (node (ref "R153") (pin "1") (pinfunction "1_1") (pintype "passive"))
    )
    (net (code "86") (name "Net-(LD6B-C)") (class "Default")
      (node (ref "LD6") (pin "3") (pinfunction "C_3") (pintype "passive"))
      (node (ref "R154") (pin "1") (pinfunction "1_1") (pintype "passive"))
    )
    (net (code "87") (name "Net-(LD7-A)") (class "Default")
      (node (ref "LD7") (pin "2") (pinfunction "A_2") (pintype "passive"))
      (node (ref "R8") (pin "2") (pinfunction "2_2") (pintype "passive"))
    )
    (net (code "88") (name "Net-(LD8A-A)") (class "Default")
      (node (ref "LD8") (pin "2") (pinfunction "A_2") (pintype "passive"))
      (node (ref "R7") (pin "2") (pinfunction "2_2") (pintype "passive"))
    )
    (net (code "89") (name "Net-(LD8B-A)") (class "Default")
      (node (ref "LD8") (pin "4") (pinfunction "A_4") (pintype "passive"))
      (node (ref "R11") (pin "2") (pinfunction "2_2") (pintype "passive"))
    )
    (net (code "90") (name "Net-(LD9-A)") (class "Default")
      (node (ref "LD9") (pin "2") (pinfunction "A_2") (pintype "passive"))
      (node (ref "R10") (pin "2") (pinfunction "2_2") (pintype "passive"))
    )
    (net (code "91") (name "Net-(T1-D)") (class "Default")
      (node (ref "R139") (pin "1") (pinfunction "1_1") (pintype "passive"))
      (node (ref "T1") (pin "3") (pinfunction "D_3") (pintype "passive"))
    )
    (net (code "92") (name "Net-(T2-D)") (class "Default")
      (node (ref "R142") (pin "1") (pinfunction "1_1") (pintype "passive"))
      (node (ref "T2") (pin "3") (pinfunction "D_3") (pintype "passive"))
    )
    (net (code "93") (name "Net-(T3-D)") (class "Default")
      (node (ref "R145") (pin "1") (pinfunction "1_1") (pintype "passive"))
      (node (ref "T3") (pin "3") (pinfunction "D_3") (pintype "passive"))
    )
    (net (code "94") (name "Net-(T4-D)") (class "Default")
      (node (ref "R148") (pin "1") (pinfunction "1_1") (pintype "passive"))
      (node (ref "T4") (pin "3") (pinfunction "D_3") (pintype "passive"))
    )
    (net (code "95") (name "Net-(T5-D)") (class "Default")
      (node (ref "R158") (pin "1") (pinfunction "1_1") (pintype "passive"))
      (node (ref "T5") (pin "3") (pinfunction "D_3") (pintype "passive"))
    )
    (net (code "96") (name "Net-(T6-D)") (class "Default")
      (node (ref "R161") (pin "1") (pinfunction "1_1") (pintype "passive"))
      (node (ref "T6") (pin "3") (pinfunction "D_3") (pintype "passive"))
    )
    (net (code "97") (name "Net-(T7-D)") (class "Default")
      (node (ref "R164") (pin "1") (pinfunction "1_1") (pintype "passive"))
      (node (ref "T7") (pin "3") (pinfunction "D_3") (pintype "passive"))
    )
    (net (code "98") (name "Net-(T8-D)") (class "Default")
      (node (ref "R168") (pin "1") (pinfunction "1_1") (pintype "passive"))
      (node (ref "T8") (pin "3") (pinfunction "D_3") (pintype "passive"))
    )
    (net (code "99") (name "P3V3") (class "Default")
      (node (ref "B5") (pin "1") (pinfunction "1_1") (pintype "bidirectional"))
      (node (ref "C14") (pin "2") (pinfunction "2_2") (pintype "passive"))
      (node (ref "C15") (pin "2") (pinfunction "2_2") (pintype "passive"))
      (node (ref "C16") (pin "2") (pinfunction "2_2") (pintype "passive"))
      (node (ref "C17") (pin "2") (pinfunction "2_2") (pintype "passive"))
      (node (ref "C18") (pin "1") (pinfunction "1_1") (pintype "passive"))
      (node (ref "C19") (pin "2") (pinfunction "2_2") (pintype "passive"))
      (node (ref "C20") (pin "2") (pinfunction "2_2") (pintype "passive"))
      (node (ref "C21") (pin "2") (pinfunction "2_2") (pintype "passive"))
      (node (ref "C22") (pin "2") (pinfunction "2_2") (pintype "passive"))
      (node (ref "C23") (pin "2") (pinfunction "2_2") (pintype "passive"))
      (node (ref "C24") (pin "2") (pinfunction "2_2") (pintype "passive"))
      (node (ref "C53") (pin "2") (pinfunction "2_2") (pintype "passive"))
      (node (ref "C54") (pin "2") (pinfunction "2_2") (pintype "passive"))
      (node (ref "C55") (pin "2") (pinfunction "2_2") (pintype "passive"))
      (node (ref "C56") (pin "2") (pinfunction "2_2") (pintype "passive"))
      (node (ref "C69") (pin "2") (pinfunction "2_2") (pintype "passive"))
      (node (ref "C70") (pin "2") (pinfunction "2_2") (pintype "passive"))
      (node (ref "C71") (pin "1") (pinfunction "1_1") (pintype "passive"))
      (node (ref "C72") (pin "2") (pinfunction "2_2") (pintype "passive"))
      (node (ref "C73") (pin "2") (pinfunction "2_2") (pintype "passive"))
      (node (ref "IC10") (pin "10") (pinfunction "EN2_10") (pintype "input"))
      (node (ref "IC10") (pin "16") (pinfunction "VDD2_16") (pintype "power_in"))
      (node (ref "IC11") (pin "1") (pinfunction "VDD1_1") (pintype "power_in"))
      (node (ref "IC11") (pin "7") (pinfunction "EN1_7") (pintype "input"))
      (node (ref "IC21") (pin "11") (pinfunction "VCC_11") (pintype "power_in"))
      (node (ref "IC21") (pin "15") (pinfunction "VCC_15") (pintype "power_in"))
      (node (ref "IC21") (pin "16") (pinfunction "VCC_16") (pintype "power_in"))
      (node (ref "IC21") (pin "2") (pinfunction "VCC_2") (pintype "power_in"))
      (node (ref "IC21") (pin "24") (pinfunction "VCC_24") (pintype "power_in"))
      (node (ref "IC21") (pin "30") (pinfunction "PDN_30") (pintype "input"))
      (node (ref "IC21") (pin "37") (pinfunction "VCC_37") (pintype "power_in"))
      (node (ref "IC21") (pin "45") (pinfunction "VCC_45") (pintype "power_in"))
      (node (ref "IC21") (pin "46") (pinfunction "VCC_46") (pintype "power_in"))
      (node (ref "IC22") (pin "10") (pinfunction "EN2_10") (pintype "input"))
      (node (ref "IC22") (pin "16") (pinfunction "VDD2_16") (pintype "power_in"))
      (node (ref "IC28") (pin "1") (pinfunction "VDD1_1") (pintype "power_in"))
      (node (ref "IC28") (pin "7") (pinfunction "EN1_7") (pintype "input"))
      (node (ref "IC30") (pin "10") (pinfunction "VOS_10") (pintype "input"))
      (node (ref "IC30") (pin "8") (pinfunction "SLEEP_8") (pintype "input"))
      (node (ref "IC9") (pin "11") (pinfunction "VCC_11") (pintype "power_in"))
      (node (ref "IC9") (pin "15") (pinfunction "VCC_15") (pintype "power_in"))
      (node (ref "IC9") (pin "16") (pinfunction "VCC_16") (pintype "power_in"))
      (node (ref "IC9") (pin "2") (pinfunction "VCC_2") (pintype "power_in"))
      (node (ref "IC9") (pin "24") (pinfunction "VCC_24") (pintype "power_in"))
      (node (ref "IC9") (pin "30") (pinfunction "PDN_30") (pintype "input"))
      (node (ref "IC9") (pin "37") (pinfunction "VCC_37") (pintype "power_in"))
      (node (ref "IC9") (pin "45") (pinfunction "VCC_45") (pintype "power_in"))
      (node (ref "IC9") (pin "46") (pinfunction "VCC_46") (pintype "power_in"))
      (node (ref "L1") (pin "2") (pinfunction "2_2") (pintype "passive"))
      (node (ref "LD5") (pin "2") (pinfunction "A_2") (pintype "passive"))
      (node (ref "LD5") (pin "4") (pinfunction "A_4") (pintype "passive"))
      (node (ref "LD6") (pin "2") (pinfunction "A_2") (pintype "passive"))
      (node (ref "LD6") (pin "4") (pinfunction "A_4") (pintype "passive"))
      (node (ref "R136") (pin "2") (pinfunction "2_2") (pintype "passive"))
      (node (ref "R137") (pin "2") (pinfunction "2_2") (pintype "passive"))
      (node (ref "R155") (pin "2") (pinfunction "2_2") (pintype "passive"))
      (node (ref "R156") (pin "2") (pinfunction "2_2") (pintype "passive"))
      (node (ref "R167") (pin "2") (pinfunction "2_2") (pintype "passive"))
      (node (ref "R8") (pin "1") (pinfunction "1_1") (pintype "passive"))
    )
    (net (code "100") (name "P3V3_MP") (class "Default")
      (node (ref "B3") (pin "1") (pinfunction "1_1") (pintype "bidirectional"))
      (node (ref "C37") (pin "2") (pinfunction "2_2") (pintype "passive"))
      (node (ref "C38") (pin "2") (pinfunction "2_2") (pintype "passive"))
      (node (ref "IC13") (pin "16") (pinfunction "VCC_16") (pintype "bidirectional"))
      (node (ref "IC13") (pin "2") (pinfunction "A1_2") (pintype "input"))
      (node (ref "IC13") (pin "3") (pinfunction "A2_3") (pintype "input"))
      (node (ref "IC32") (pin "4") (pinfunction "VCC_4") (pintype "power_in"))
      (node (ref "J37") (pin "30") (pinfunction "30_30") (pintype "bidirectional"))
      (node (ref "R10") (pin "1") (pinfunction "1_1") (pintype "passive"))
    )
    (net (code "101") (name "P5V0_ISO1") (class "Default")
      (node (ref "B9") (pin "1") (pinfunction "1_1") (pintype "bidirectional"))
      (node (ref "C48") (pin "2") (pinfunction "2_2") (pintype "passive"))
      (node (ref "C49") (pin "2") (pinfunction "2_2") (pintype "passive"))
      (node (ref "C50") (pin "2") (pinfunction "2_2") (pintype "passive"))
      (node (ref "C51") (pin "2") (pinfunction "2_2") (pintype "passive"))
      (node (ref "C52") (pin "1") (pinfunction "1_1") (pintype "passive"))
      (node (ref "IC2") (pin "8") (pinfunction "+Vout_8") (pintype "power_in"))
      (node (ref "IC22") (pin "1") (pinfunction "VDD1_1") (pintype "power_in"))
      (node (ref "IC22") (pin "7") (pinfunction "EN1_7") (pintype "input"))
      (node (ref "IC28") (pin "10") (pinfunction "EN2_10") (pintype "input"))
      (node (ref "IC28") (pin "16") (pinfunction "VDD2_16") (pintype "power_in"))
      (node (ref "IC29") (pin "16") (pinfunction "VCC_16") (pintype "power_in"))
      (node (ref "IC29") (pin "21") (pinfunction "VCC_21") (pintype "power_in"))
      (node (ref "IC31") (pin "6") (pinfunction "+Vout_6") (pintype "power_in"))
      (node (ref "R150") (pin "2") (pinfunction "2_2") (pintype "passive"))
      (node (ref "SW1") (pin "1") (pinfunction "1_1") (pintype "passive"))
      (node (ref "SW1") (pin "2") (pinfunction "2_2") (pintype "passive"))
      (node (ref "SW1") (pin "3") (pinfunction "3_3") (pintype "passive"))
      (node (ref "SW1") (pin "4") (pinfunction "4_4") (pintype "passive"))
    )
    (net (code "102") (name "P5V0_ISO2") (class "Default")
      (node (ref "B11") (pin "1") (pinfunction "1_1") (pintype "bidirectional"))
      (node (ref "C28") (pin "2") (pinfunction "2_2") (pintype "passive"))
      (node (ref "C29") (pin "2") (pinfunction "2_2") (pintype "passive"))
      (node (ref "C30") (pin "2") (pinfunction "2_2") (pintype "passive"))
      (node (ref "C31") (pin "2") (pinfunction "2_2") (pintype "passive"))
      (node (ref "C32") (pin "1") (pinfunction "1_1") (pintype "passive"))
      (node (ref "IC1") (pin "8") (pinfunction "+Vout_8") (pintype "power_in"))
      (node (ref "IC10") (pin "1") (pinfunction "VDD1_1") (pintype "power_in"))
      (node (ref "IC10") (pin "7") (pinfunction "EN1_7") (pintype "input"))
      (node (ref "IC11") (pin "10") (pinfunction "EN2_10") (pintype "input"))
      (node (ref "IC11") (pin "16") (pinfunction "VDD2_16") (pintype "power_in"))
      (node (ref "IC12") (pin "6") (pinfunction "+Vout_6") (pintype "power_in"))
      (node (ref "IC8") (pin "16") (pinfunction "VCC_16") (pintype "power_in"))
      (node (ref "IC8") (pin "21") (pinfunction "VCC_21") (pintype "power_in"))
      (node (ref "R172") (pin "2") (pinfunction "2_2") (pintype "passive"))
      (node (ref "SW2") (pin "1") (pinfunction "1_1") (pintype "passive"))
      (node (ref "SW2") (pin "2") (pinfunction "2_2") (pintype "passive"))
      (node (ref "SW2") (pin "3") (pinfunction "3_3") (pintype "passive"))
      (node (ref "SW2") (pin "4") (pinfunction "4_4") (pintype "passive"))
    )
    (net (code "103") (name "P12V0") (class "Default")
      (node (ref "B6") (pin "1") (pinfunction "1_1") (pintype "bidirectional"))
      (node (ref "C33") (pin "2") (pinfunction "2_2") (pintype "passive"))
      (node (ref "C34") (pin "1") (pinfunction "1_1") (pintype "passive"))
      (node (ref "C35") (pin "2") (pinfunction "2_2") (pintype "passive"))
      (node (ref "C36") (pin "1") (pinfunction "1_1") (pintype "passive"))
      (node (ref "C74") (pin "2") (pinfunction "2_2") (pintype "passive"))
      (node (ref "C75") (pin "2") (pinfunction "2_2") (pintype "passive"))
      (node (ref "IC1") (pin "3") (pinfunction "+Vin_3") (pintype "power_in"))
      (node (ref "IC12") (pin "1") (pinfunction "+Vin_1") (pintype "power_in"))
      (node (ref "IC2") (pin "3") (pinfunction "+Vin_3") (pintype "power_in"))
      (node (ref "IC30") (pin "2") (pinfunction "VIN_2") (pintype "input"))
      (node (ref "IC30") (pin "3") (pinfunction "EN_3") (pintype "input"))
      (node (ref "IC31") (pin "1") (pinfunction "+Vin_1") (pintype "power_in"))
      (node (ref "J37") (pin "28") (pinfunction "28_28") (pintype "bidirectional"))
      (node (ref "J37") (pin "29") (pinfunction "29_29") (pintype "bidirectional"))
      (node (ref "R6") (pin "2") (pinfunction "2_2") (pintype "passive"))
    )
    (net (code "104") (name "unconnected-(IC1-na-Pad14)") (class "Default")
      (node (ref "IC1") (pin "14") (pinfunction "na_14") (pintype "passive"))
    )
    (net (code "105") (name "unconnected-(IC2-na-Pad14)") (class "Default")
      (node (ref "IC2") (pin "14") (pinfunction "na_14") (pintype "passive"))
    )
    (net (code "106") (name "unconnected-(IC9-NC-Pad17)") (class "Default")
      (node (ref "IC9") (pin "17") (pinfunction "NC_17") (pintype "passive"))
    )
    (net (code "107") (name "unconnected-(IC9-NC-Pad44)") (class "Default")
      (node (ref "IC9") (pin "44") (pinfunction "NC_44") (pintype "passive"))
    )
    (net (code "108") (name "unconnected-(IC13-~{INT}-Pad13)") (class "Default")
      (node (ref "IC13") (pin "13") (pinfunction "~{INT}_13") (pintype "output"))
    )
    (net (code "109") (name "unconnected-(IC21-NC-Pad17)") (class "Default")
      (node (ref "IC21") (pin "17") (pinfunction "NC_17") (pintype "passive"))
    )
    (net (code "110") (name "unconnected-(IC21-NC-Pad44)") (class "Default")
      (node (ref "IC21") (pin "44") (pinfunction "NC_44") (pintype "passive"))
    )
    (net (code "111") (name "unconnected-(IC30-NC-Pad4)") (class "Default")
      (node (ref "IC30") (pin "4") (pinfunction "NC_4") (pintype "passive"))
    )
    (net (code "112") (name "unconnected-(IC30-PG-Pad7)") (class "Default")
      (node (ref "IC30") (pin "7") (pinfunction "PG_7") (pintype "output"))
    )
    (net (code "113") (name "unconnected-(IC32-NC-Pad5)") (class "Default")
      (node (ref "IC32") (pin "5") (pinfunction "NC_5") (pintype "passive"))
    )
  )
)
